# CPU.net
KiCad netlist of a schematic drawn in Altium Designer
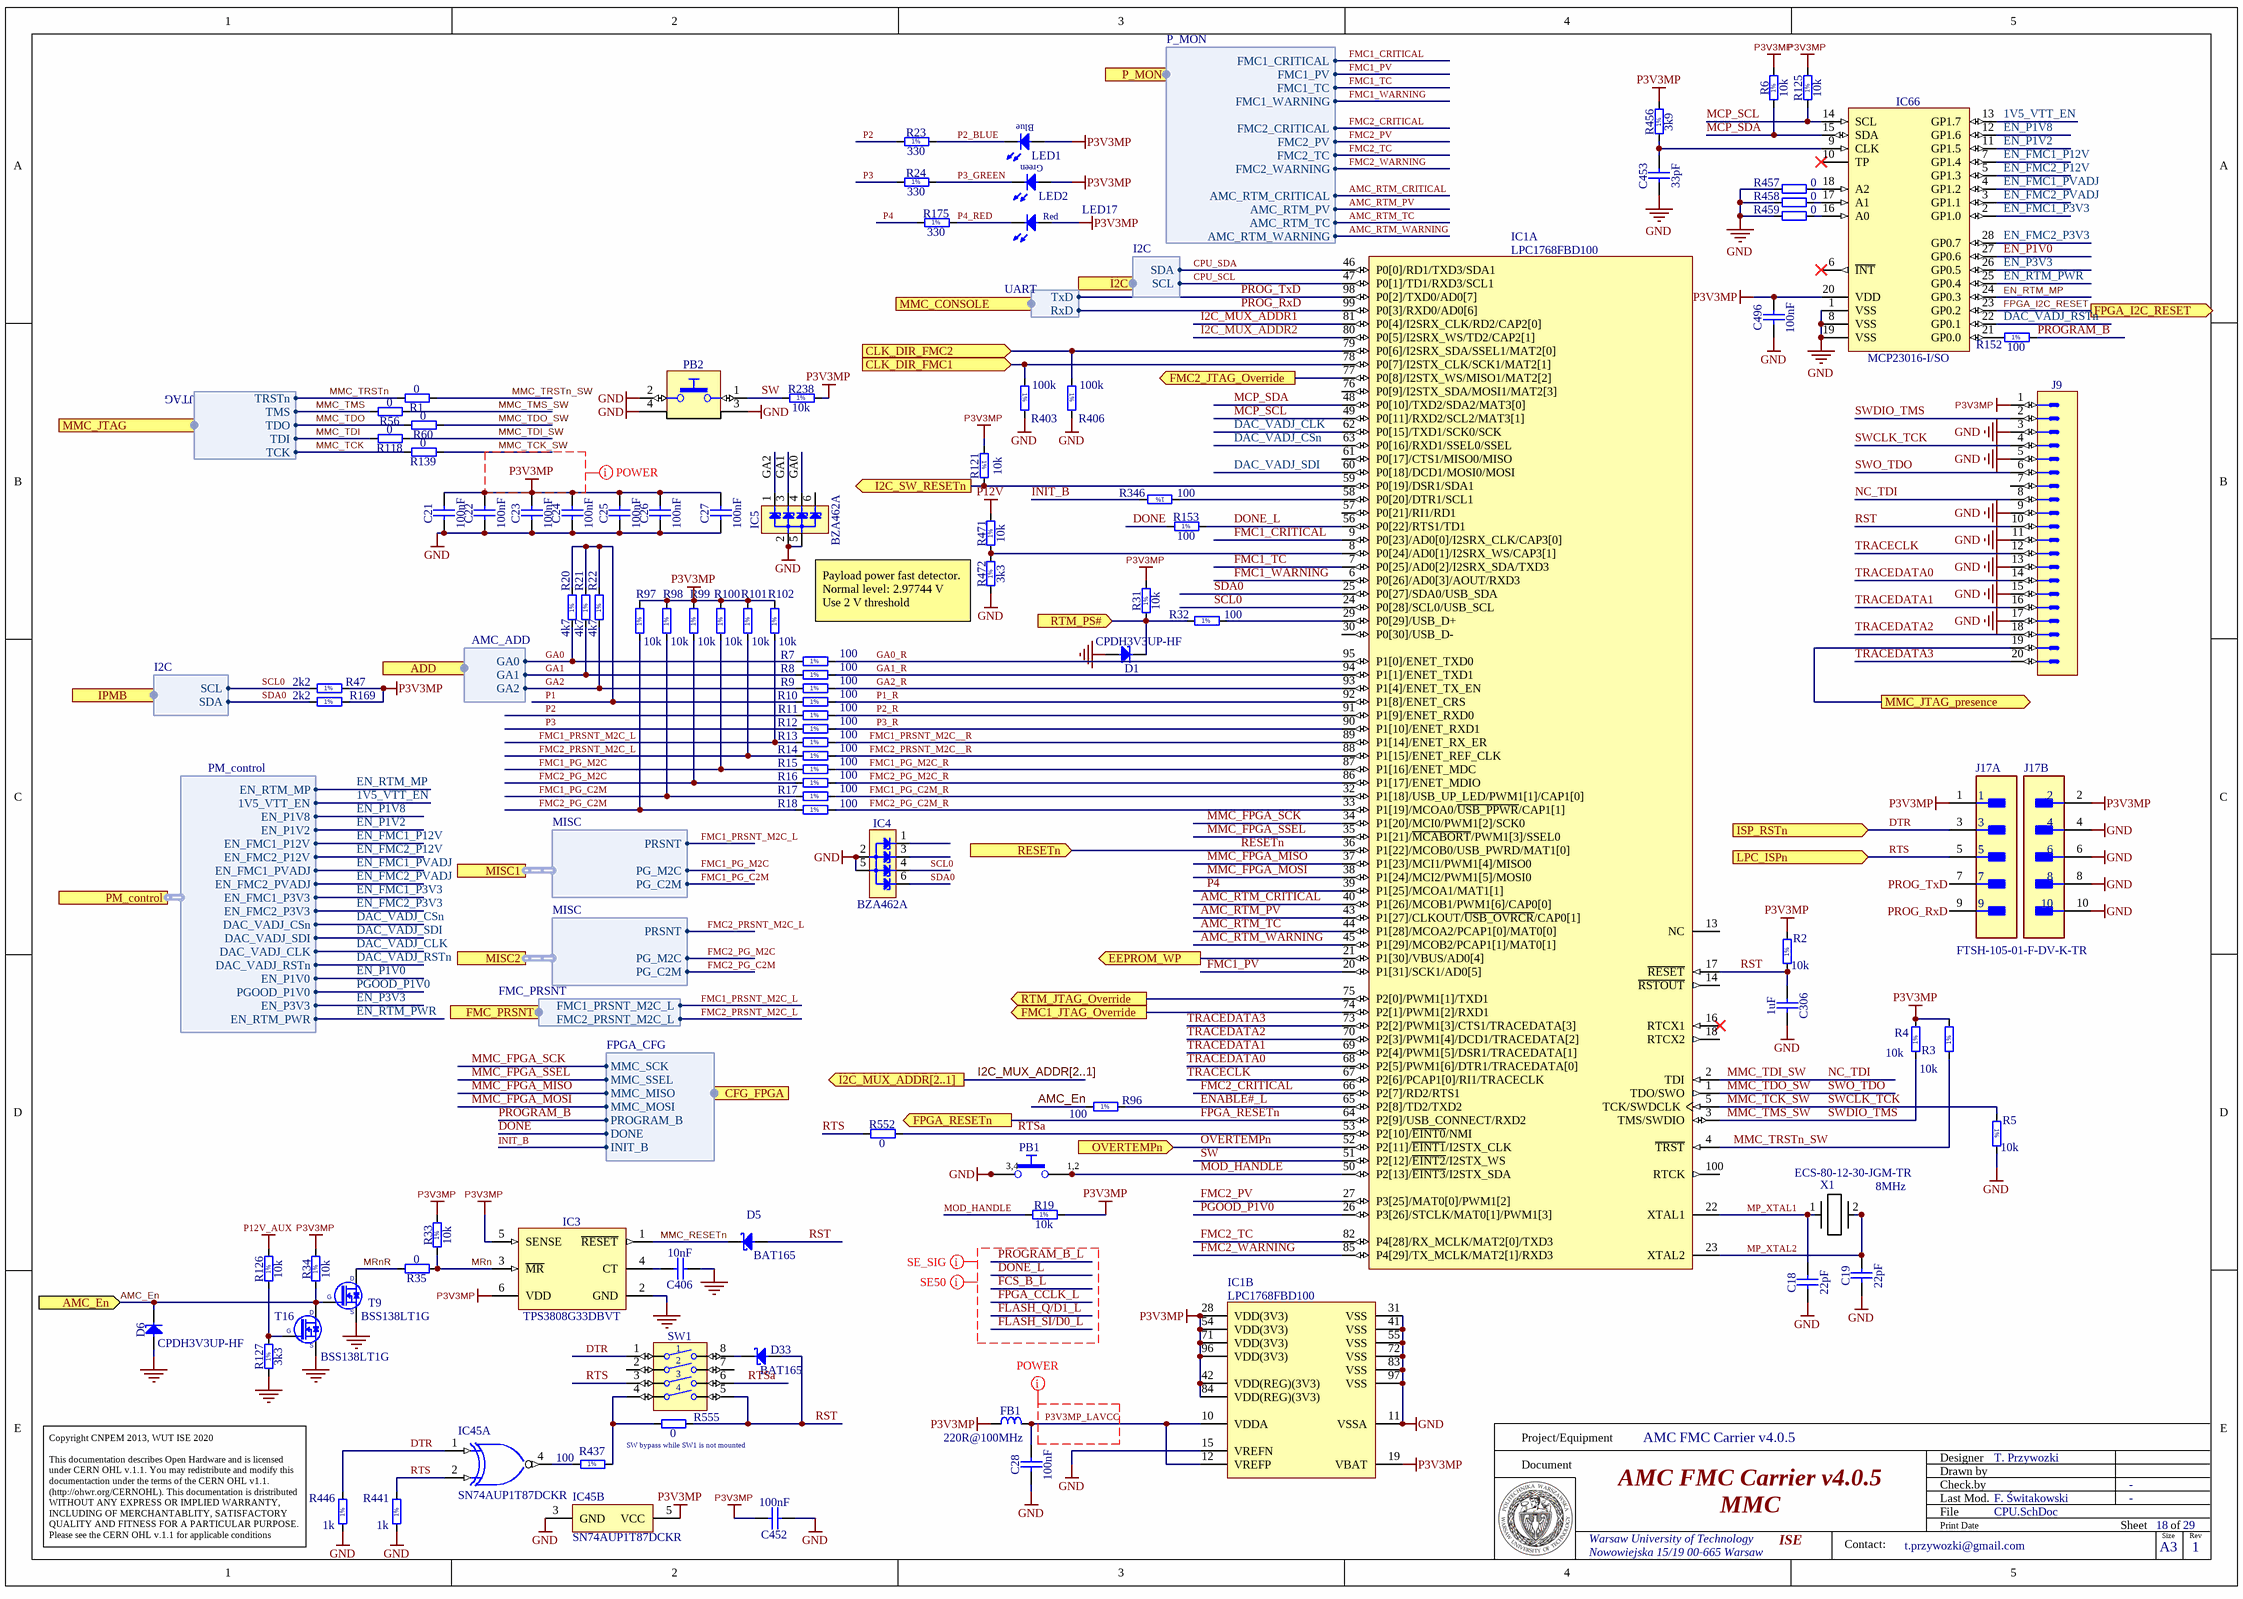
[diagram p0: CPU.SchDoc]

(export (version "E")
  (design (tool "Eeschema 10.0.6"))
  (components
    (comp (ref "C18")
      (value "22pF")
      (footprint "CAPC1005X55N")
      (description "Non-polarised capacitor")
      (fields
        (field (name "PART NUMBER") "CC0402_22PF_50V_5%_NP0")
        (field (name "VOLTAGE") "50V")
        (field (name "AUTHOR") "CERN DEM JLC")
      )
      (libsource (lib "Capacitors") (part "Capacitor - non polarized"))
    )
    (comp (ref "C19")
      (value "22pF")
      (footprint "CAPC1005X55N")
      (description "Non-polarised capacitor")
      (fields
        (field (name "PART NUMBER") "CC0402_22PF_50V_5%_NP0")
        (field (name "VOLTAGE") "50V")
        (field (name "AUTHOR") "CERN DEM JLC")
      )
      (libsource (lib "Capacitors") (part "Capacitor - non polarized"))
    )
    (comp (ref "C21")
      (value "100nF")
      (footprint "CAPC0603X33N")
      (description "Non-polarised capacitor")
      (fields
        (field (name "PART NUMBER") "CC0201_100NF_6.3V_10%_X5R")
        (field (name "VOLTAGE") "6.3V")
        (field (name "AUTHOR") "CERN DEM JLC")
      )
      (libsource (lib "Capacitors") (part "Capacitor - non polarized"))
    )
    (comp (ref "C22")
      (value "100nF")
      (footprint "CAPC0603X33N")
      (description "Non-polarised capacitor")
      (fields
        (field (name "PART NUMBER") "CC0201_100NF_6.3V_10%_X5R")
        (field (name "VOLTAGE") "6.3V")
        (field (name "AUTHOR") "CERN DEM JLC")
      )
      (libsource (lib "Capacitors") (part "Capacitor - non polarized"))
    )
    (comp (ref "C23")
      (value "100nF")
      (footprint "CAPC0603X33N")
      (description "Non-polarised capacitor")
      (fields
        (field (name "PART NUMBER") "CC0201_100NF_6.3V_10%_X5R")
        (field (name "VOLTAGE") "6.3V")
        (field (name "AUTHOR") "CERN DEM JLC")
      )
      (libsource (lib "Capacitors") (part "Capacitor - non polarized"))
    )
    (comp (ref "C24")
      (value "100nF")
      (footprint "CAPC0603X33N")
      (description "Non-polarised capacitor")
      (fields
        (field (name "PART NUMBER") "CC0201_100NF_6.3V_10%_X5R")
        (field (name "VOLTAGE") "6.3V")
        (field (name "AUTHOR") "CERN DEM JLC")
      )
      (libsource (lib "Capacitors") (part "Capacitor - non polarized"))
    )
    (comp (ref "C25")
      (value "100nF")
      (footprint "CAPC0603X33N")
      (description "Non-polarised capacitor")
      (fields
        (field (name "PART NUMBER") "CC0201_100NF_6.3V_10%_X5R")
        (field (name "VOLTAGE") "6.3V")
        (field (name "AUTHOR") "CERN DEM JLC")
      )
      (libsource (lib "Capacitors") (part "Capacitor - non polarized"))
    )
    (comp (ref "C26")
      (value "100nF")
      (footprint "CAPC0603X33N")
      (description "Non-polarised capacitor")
      (fields
        (field (name "PART NUMBER") "CC0201_100NF_6.3V_10%_X5R")
        (field (name "VOLTAGE") "6.3V")
        (field (name "AUTHOR") "CERN DEM JLC")
      )
      (libsource (lib "Capacitors") (part "Capacitor - non polarized"))
    )
    (comp (ref "C27")
      (value "100nF")
      (footprint "CAPC0603X33N")
      (description "Non-polarised capacitor")
      (fields
        (field (name "PART NUMBER") "CC0201_100NF_6.3V_10%_X5R")
        (field (name "VOLTAGE") "6.3V")
        (field (name "AUTHOR") "CERN DEM JLC")
      )
      (libsource (lib "Capacitors") (part "Capacitor - non polarized"))
    )
    (comp (ref "C28")
      (value "100nF")
      (footprint "CAPC0603X33N")
      (description "Non-polarised capacitor")
      (fields
        (field (name "PART NUMBER") "CC0201_100NF_6.3V_10%_X5R")
        (field (name "VOLTAGE") "6.3V")
        (field (name "AUTHOR") "CERN DEM JLC")
      )
      (libsource (lib "Capacitors") (part "Capacitor - non polarized"))
    )
    (comp (ref "C306")
      (value "1uF")
      (footprint "CAPC1608X87N")
      (description "Non-polarised capacitor")
      (fields
        (field (name "PART NUMBER") "CC0603_1UF_16V_10%_X7R")
        (field (name "VOLTAGE") "16V")
        (field (name "AUTHOR") "CERN DEM JLC")
      )
      (libsource (lib "Capacitors") (part "Capacitor - non polarized"))
    )
    (comp (ref "C406")
      (value "10nF")
      (footprint "CAPC1005X55N")
      (description "Non-polarised capacitor")
      (fields
        (field (name "MANUFACTURER PART NUMBER") "CC0402_10NF_16V_10%_X7R")
        (field (name "MANUFACTURER") "GENERIC")
        (field (name "AUTHOR") "CERN DEM JLC")
      )
      (libsource (lib "Capacitors") (part "Capacitor - non polarized"))
    )
    (comp (ref "C452")
      (value "100nF")
      (footprint "CAPC0603X33N")
      (description "Non-polarised capacitor")
      (fields
        (field (name "PART NUMBER") "CC0201_100NF_6.3V_10%_X5R")
        (field (name "VOLTAGE") "6.3V")
        (field (name "AUTHOR") "CERN DEM JLC")
      )
      (libsource (lib "Capacitors") (part "Capacitor - non polarized"))
    )
    (comp (ref "C453")
      (value "33pF")
      (footprint "CAPC1005X55N")
      (description "Non-polarised capacitor")
      (fields
        (field (name "PART NUMBER") "CC0402_33PF_50V_5%_C0G")
        (field (name "VOLTAGE") "50V")
        (field (name "AUTHOR") "CERN DEM JLC")
      )
      (libsource (lib "Capacitors") (part "Capacitor - non polarized"))
    )
    (comp (ref "C496")
      (value "100nF")
      (footprint "CAPC0603X33N")
      (description "Non-polarised capacitor")
      (fields
        (field (name "PART NUMBER") "CC0201_100NF_6.3V_10%_X5R")
        (field (name "VOLTAGE") "6.3V")
        (field (name "AUTHOR") "CERN DEM JLC")
      )
      (libsource (lib "Capacitors") (part "Capacitor - non polarized"))
    )
    (comp (ref "D1")
      (value "CPDH3V3UP-HF")
      (footprint "SODFL1608X65N")
      (description "ESD protection diode")
      (fields (field (name "MANUFACTURER") "Comchip Technology") (field (name "AUTHOR") "CERN DEM JLC"))
      (libsource (lib "ICs And Semiconductors") (part "Diode ESD"))
    )
    (comp (ref "D5")
      (value "BAT165")
      (footprint "SOD2512X110N")
      (description "Schottky Diode")
      (fields
        (field (name "MANUFACTURER") "INFINEON")
        (field (name "VOLTAGE") "40V")
        (field (name "AUTHOR") "CERN DEM JLC")
      )
      (libsource (lib "ICs And Semiconductors") (part "Diode Schottky"))
    )
    (comp (ref "D6")
      (value "CPDH3V3UP-HF")
      (footprint "SODFL1608X65N")
      (description "ESD protection diode")
      (fields (field (name "MANUFACTURER") "Comchip Technology") (field (name "AUTHOR") "CERN DEM JLC"))
      (libsource (lib "ICs And Semiconductors") (part "Diode ESD"))
    )
    (comp (ref "D33")
      (value "BAT165")
      (footprint "SOD2512X110N")
      (description "Schottky Diode")
      (fields
        (field (name "MANUFACTURER") "INFINEON")
        (field (name "VOLTAGE") "40V")
        (field (name "AUTHOR") "CERN DEM JLC")
      )
      (libsource (lib "ICs And Semiconductors") (part "Diode Schottky"))
    )
    (comp (ref "FB1")
      (value "220R@100MHz")
      (footprint "INDC2012X105N")
      (description "Inductor")
      (fields
        (field (name "PART NUMBER") "IND0805_MURATA_BLM21PG221SN1D")
        (field (name "POWER") "2A")
        (field (name "AUTHOR") "CERN DEM JLC")
      )
      (libsource (lib "Inductors & Transformers") (part "Inductor"))
    )
    (comp (ref "IC1")
      (value "LPC1768FBD100")
      (footprint "QFP50P1600X1600X160-100N")
      (description "LPC1768 Series 64kB 100MHz 32-Bit ARM Cortex-M3 Microcontroller")
      (fields (field (name "MANUFACTURER") "NXP SEMICONDUCTORS") (field (name "AUTHOR") "CERN DEM JLC"))
      (libsource (lib "ICs And Semiconductors") (part "LPC1768FBD100"))
    )
    (comp (ref "IC3")
      (value "TPS3808G33DBVT")
      (footprint "SOT95P280X145-6N")
      (description "Low Quiescent Current, Programmable-Delay Supervisory Circuit")
      (fields (field (name "MANUFACTURER") "TEXAS INSTRUMENTS") (field (name "AUTHOR") "CERN DEM JLC"))
      (libsource (lib "ICs And Semiconductors") (part "TPS3808xxxDBV"))
    )
    (comp (ref "IC4")
      (value "BZA462A")
      (footprint "SOT95P275X110-6N")
      (description "Quadruple ESD Transient Voltage Suppressor")
      (fields
        (field (name "VOLTAGE") "15kV")
        (field (name "POWER") "24W")
        (field (name "AUTHOR") "CERN DEM JLC")
      )
      (libsource (lib "ICs And Semiconductors") (part "BZA462A"))
    )
    (comp (ref "IC5")
      (value "BZA462A")
      (footprint "SOT95P275X110-6N")
      (description "Quadruple ESD Transient Voltage Suppressor")
      (fields
        (field (name "VOLTAGE") "15kV")
        (field (name "POWER") "24W")
        (field (name "AUTHOR") "CERN DEM JLC")
      )
      (libsource (lib "") (part "BZA462A_1"))
    )
    (comp (ref "IC45")
      (value "SN74AUP1T87DCKR")
      (footprint "DCK0005A_L")
      (fields
        (field (name "GENERIC PART NUMBER") "SN74AUP1T87")
        (field (name "MANUFACTURER") "Texas Instruments")
      )
      (libsource (lib "") (part "TI-SN74AUP1T87-DCK0005A-5_1"))
    )
    (comp (ref "IC66")
      (value "MCP23016-I/SO")
      (footprint "SOIC127P1030X265-28N")
      (description "16-bit I/O I2C I/O Expander")
      (fields (field (name "MANUFACTURER") "MICROCHIP TECHNOLOGY") (field (name "AUTHOR") "CERN DEM JLC"))
      (libsource (lib "ICs And Semiconductors") (part "MCP23016-I/SO"))
    )
    (comp (ref "J9")
      (value "Header 20")
      (footprint "SAMTEC_FTSH-110-01-F-DV-K")
      (description "Connector 20 Male")
      (fields
        (field (name "PART NUMBER") "SAMTEC_FTSH-110-01-F-DV-K")
        (field (name "MANUFACTURER") "SAMTEC")
        (field (name "AUTHOR") "CERN DEM JLC")
      )
      (libsource (lib "Connectors") (part "Connector 20 Male"))
    )
    (comp (ref "J17")
      (value "FTSH-105-01-F-DV-K-TR")
      (footprint "FP-FTSH-105-01-F-DV-K-TR-MFG")
      (description "CONN HEADER SMD 10POS 1.27MM")
      (libsource (lib "") (part "544f42128f4185dcb88ce1ce9bf1982_1"))
    )
    (comp (ref "LED1")
      (value "Blue")
      (footprint "LED_AVAGO_HSME-C120rev")
      (description "LED Blue Avago C120")
      (fields
        (field (name "PART NUMBER") "LED_AVAGO_HSMR-C120")
        (field (name "MANUFACTURER") "AVAGO TECHNOLOGIES")
        (field (name "AUTHOR") "CERN DEM JMW")
      )
      (libsource (lib "LIBRARY_SCH") (part "LED_SMD_90deg_mini_B"))
    )
    (comp (ref "LED2")
      (value "Green")
      (footprint "LED_AVAGO_HSME-C120rev")
      (description "LED Green Avago C120")
      (fields
        (field (name "PART NUMBER") "LED_AVAGO_HSME-C120")
        (field (name "MANUFACTURER") "AVAGO TECHNOLOGIES")
        (field (name "AUTHOR") "CERN DEM JMW")
      )
      (libsource (lib "LIBRARY_SCH") (part "LED_SMD_90deg_mini_G"))
    )
    (comp (ref "LED17")
      (value "Red")
      (footprint "LED_KINGBRIGHT_KPH-1608SURCK")
      (description "LED Red 1C 2A")
      (fields
        (field (name "PART NUMBER") "LED_KINGBRIGHT_KPH-1608SURCK")
        (field (name "MANUFACTURER") "KINGBRIGHT")
        (field (name "AUTHOR") "CERN DEM JLC")
      )
      (libsource (lib "ICs And Semiconductors") (part "LED Red 1C 2A"))
    )
    (comp (ref "PB1")
      (value "Push Button")
      (footprint "SW_C&K_HDT0001")
      (description "Push-Button Switch SPDT")
      (fields
        (field (name "PART NUMBER") "SW_C&K_HDT0001")
        (field (name "MANUFACTURER") "C&K")
        (field (name "AUTHOR") "CERN DEM JLC")
      )
      (libsource (lib "Eletro-mechanical") (part "PB SPST 12NO-34NO"))
    )
    (comp (ref "PB2")
      (value "Push Button")
      (footprint "PB_ALPS_SKHHLMA010")
      (description "Push-Button Switch SPDT")
      (fields
        (field (name "PART NUMBER") "PB_ALPS_SKHHLMA010")
        (field (name "MANUFACTURER") "ALPS")
        (field (name "AUTHOR") "CERN DEM JLC")
      )
      (libsource (lib "Eletro-mechanical") (part "PB SPST 1NO-2NO 34CASE"))
    )
    (comp (ref "R1")
      (value "0")
      (footprint "RESC1005X40N")
      (description "Resistor")
      (fields
        (field (name "MANUFACTURER PART NUMBER") "R0402_0R_JUMPER")
        (field (name "MANUFACTURER") "GENERIC")
        (field (name "AUTHOR") "CERN DEM JLC")
      )
      (libsource (lib "Resistors") (part "Resistor"))
    )
    (comp (ref "R2")
      (value "10k")
      (footprint "RESC1005X40N")
      (description "Resistor - 1%")
      (fields
        (field (name "PART NUMBER") "R0402_10K_1%_0.0625W_100PPM")
        (field (name "POWER") "0.0625W")
        (field (name "AUTHOR") "CERN DEM JLC")
      )
      (libsource (lib "Resistors") (part "Resistor - 1%"))
    )
    (comp (ref "R3")
      (value "10k")
      (footprint "RESC1005X40N")
      (description "Resistor - 1%")
      (fields
        (field (name "PART NUMBER") "R0402_10K_1%_0.0625W_100PPM")
        (field (name "POWER") "0.0625W")
        (field (name "AUTHOR") "CERN DEM JLC")
      )
      (libsource (lib "Resistors") (part "Resistor - 1%"))
    )
    (comp (ref "R4")
      (value "10k")
      (footprint "RESC1005X40N")
      (description "Resistor - 1%")
      (fields
        (field (name "PART NUMBER") "R0402_10K_1%_0.0625W_100PPM")
        (field (name "POWER") "0.0625W")
        (field (name "AUTHOR") "CERN DEM JLC")
      )
      (libsource (lib "Resistors") (part "Resistor - 1%"))
    )
    (comp (ref "R5")
      (value "10k")
      (footprint "RESC1005X40N")
      (description "Resistor - 1%")
      (fields
        (field (name "PART NUMBER") "R0402_10K_1%_0.0625W_100PPM")
        (field (name "POWER") "0.0625W")
        (field (name "AUTHOR") "CERN DEM JLC")
      )
      (libsource (lib "Resistors") (part "Resistor - 1%"))
    )
    (comp (ref "R6")
      (value "10k")
      (footprint "RESC1005X40N")
      (description "Resistor - 1%")
      (fields
        (field (name "MANUFACTURER PART NUMBER") "R0402_10K_1%_0.0625W_100PPM")
        (field (name "MANUFACTURER") "GENERIC")
        (field (name "AUTHOR") "CERN DEM JLC")
      )
      (libsource (lib "Resistors") (part "Resistor - 1%"))
    )
    (comp (ref "R7")
      (value "100")
      (footprint "RESC1005X40N")
      (description "Resistor - 1%")
      (fields
        (field (name "PART NUMBER") "R0402_100R_1%_0.0625W_100PPM")
        (field (name "POWER") "0.0625W")
        (field (name "AUTHOR") "CERN DEM JLC")
      )
      (libsource (lib "Resistors") (part "Resistor - 1%"))
    )
    (comp (ref "R8")
      (value "100")
      (footprint "RESC1005X40N")
      (description "Resistor - 1%")
      (fields
        (field (name "PART NUMBER") "R0402_100R_1%_0.0625W_100PPM")
        (field (name "POWER") "0.0625W")
        (field (name "AUTHOR") "CERN DEM JLC")
      )
      (libsource (lib "Resistors") (part "Resistor - 1%"))
    )
    (comp (ref "R9")
      (value "100")
      (footprint "RESC1005X40N")
      (description "Resistor - 1%")
      (fields
        (field (name "PART NUMBER") "R0402_100R_1%_0.0625W_100PPM")
        (field (name "POWER") "0.0625W")
        (field (name "AUTHOR") "CERN DEM JLC")
      )
      (libsource (lib "Resistors") (part "Resistor - 1%"))
    )
    (comp (ref "R10")
      (value "100")
      (footprint "RESC1005X40N")
      (description "Resistor - 1%")
      (fields
        (field (name "PART NUMBER") "R0402_100R_1%_0.0625W_100PPM")
        (field (name "POWER") "0.0625W")
        (field (name "AUTHOR") "CERN DEM JLC")
      )
      (libsource (lib "Resistors") (part "Resistor - 1%"))
    )
    (comp (ref "R11")
      (value "100")
      (footprint "RESC1005X40N")
      (description "Resistor - 1%")
      (fields
        (field (name "PART NUMBER") "R0402_100R_1%_0.0625W_100PPM")
        (field (name "POWER") "0.0625W")
        (field (name "AUTHOR") "CERN DEM JLC")
      )
      (libsource (lib "Resistors") (part "Resistor - 1%"))
    )
    (comp (ref "R12")
      (value "100")
      (footprint "RESC1005X40N")
      (description "Resistor - 1%")
      (fields
        (field (name "PART NUMBER") "R0402_100R_1%_0.0625W_100PPM")
        (field (name "POWER") "0.0625W")
        (field (name "AUTHOR") "CERN DEM JLC")
      )
      (libsource (lib "Resistors") (part "Resistor - 1%"))
    )
    (comp (ref "R13")
      (value "100")
      (footprint "RESC1005X40N")
      (description "Resistor - 1%")
      (fields
        (field (name "PART NUMBER") "R0402_100R_1%_0.0625W_100PPM")
        (field (name "POWER") "0.0625W")
        (field (name "AUTHOR") "CERN DEM JLC")
      )
      (libsource (lib "Resistors") (part "Resistor - 1%"))
    )
    (comp (ref "R14")
      (value "100")
      (footprint "RESC1005X40N")
      (description "Resistor - 1%")
      (fields
        (field (name "PART NUMBER") "R0402_100R_1%_0.0625W_100PPM")
        (field (name "POWER") "0.0625W")
        (field (name "AUTHOR") "CERN DEM JLC")
      )
      (libsource (lib "Resistors") (part "Resistor - 1%"))
    )
    (comp (ref "R15")
      (value "100")
      (footprint "RESC1005X40N")
      (description "Resistor - 1%")
      (fields
        (field (name "PART NUMBER") "R0402_100R_1%_0.0625W_100PPM")
        (field (name "POWER") "0.0625W")
        (field (name "AUTHOR") "CERN DEM JLC")
      )
      (libsource (lib "Resistors") (part "Resistor - 1%"))
    )
    (comp (ref "R16")
      (value "100")
      (footprint "RESC1005X40N")
      (description "Resistor - 1%")
      (fields
        (field (name "PART NUMBER") "R0402_100R_1%_0.0625W_100PPM")
        (field (name "POWER") "0.0625W")
        (field (name "AUTHOR") "CERN DEM JLC")
      )
      (libsource (lib "Resistors") (part "Resistor - 1%"))
    )
    (comp (ref "R17")
      (value "100")
      (footprint "RESC1005X40N")
      (description "Resistor - 1%")
      (fields
        (field (name "PART NUMBER") "R0402_100R_1%_0.0625W_100PPM")
        (field (name "POWER") "0.0625W")
        (field (name "AUTHOR") "CERN DEM JLC")
      )
      (libsource (lib "Resistors") (part "Resistor - 1%"))
    )
    (comp (ref "R18")
      (value "100")
      (footprint "RESC1005X40N")
      (description "Resistor - 1%")
      (fields
        (field (name "PART NUMBER") "R0402_100R_1%_0.0625W_100PPM")
        (field (name "POWER") "0.0625W")
        (field (name "AUTHOR") "CERN DEM JLC")
      )
      (libsource (lib "Resistors") (part "Resistor - 1%"))
    )
    (comp (ref "R19")
      (value "10k")
      (footprint "RESC1005X40N")
      (description "Resistor - 1%")
      (fields
        (field (name "PART NUMBER") "R0402_10K_1%_0.0625W_100PPM")
        (field (name "POWER") "0.0625W")
        (field (name "AUTHOR") "CERN DEM JLC")
      )
      (libsource (lib "Resistors") (part "Resistor - 1%"))
    )
    (comp (ref "R20")
      (value "4k7")
      (footprint "RESC1005X40N")
      (description "Resistor - 1%")
      (fields
        (field (name "PART NUMBER") "R0402_4K7_1%_0.0625W_100PPM")
        (field (name "POWER") "0.0625W")
        (field (name "AUTHOR") "CERN DEM JLC")
      )
      (libsource (lib "Resistors") (part "Resistor - 1%"))
    )
    (comp (ref "R21")
      (value "4k7")
      (footprint "RESC1005X40N")
      (description "Resistor - 1%")
      (fields
        (field (name "PART NUMBER") "R0402_4K7_1%_0.0625W_100PPM")
        (field (name "POWER") "0.0625W")
        (field (name "AUTHOR") "CERN DEM JLC")
      )
      (libsource (lib "Resistors") (part "Resistor - 1%"))
    )
    (comp (ref "R22")
      (value "4k7")
      (footprint "RESC1005X40N")
      (description "Resistor - 1%")
      (fields
        (field (name "PART NUMBER") "R0402_4K7_1%_0.0625W_100PPM")
        (field (name "POWER") "0.0625W")
        (field (name "AUTHOR") "CERN DEM JLC")
      )
      (libsource (lib "Resistors") (part "Resistor - 1%"))
    )
    (comp (ref "R23")
      (value "330")
      (footprint "RESC1005X40N")
      (description "Resistor - 1%")
      (fields
        (field (name "PART NUMBER") "R0402_330R_1%_0.0625W_100PPM")
        (field (name "POWER") "0.0625W")
        (field (name "AUTHOR") "CERN DEM JLC")
      )
      (libsource (lib "Resistors") (part "Resistor - 1%"))
    )
    (comp (ref "R24")
      (value "330")
      (footprint "RESC1005X40N")
      (description "Resistor - 1%")
      (fields
        (field (name "PART NUMBER") "R0402_330R_1%_0.0625W_100PPM")
        (field (name "POWER") "0.0625W")
        (field (name "AUTHOR") "CERN DEM JLC")
      )
      (libsource (lib "Resistors") (part "Resistor - 1%"))
    )
    (comp (ref "R31")
      (value "10k")
      (footprint "RESC1005X40N")
      (description "Resistor - 1%")
      (fields
        (field (name "MANUFACTURER PART NUMBER") "R0402_10K_1%_0.0625W_100PPM")
        (field (name "MANUFACTURER") "GENERIC")
        (field (name "AUTHOR") "CERN DEM JLC")
      )
      (libsource (lib "Resistors") (part "Resistor - 1%"))
    )
    (comp (ref "R32")
      (value "100")
      (footprint "RESC1005X40N")
      (description "Resistor - 1%")
      (fields
        (field (name "MANUFACTURER PART NUMBER") "R0402_100R_1%_0.1W_100PPM_50V")
        (field (name "MANUFACTURER") "GENERIC")
        (field (name "AUTHOR") "CERN DEM JLC")
      )
      (libsource (lib "Resistors") (part "Resistor - 1%"))
    )
    (comp (ref "R33")
      (value "10k")
      (footprint "RESC1005X40N")
      (description "Resistor - 1%")
      (fields
        (field (name "MANUFACTURER PART NUMBER") "R0402_10K_1%_0.0625W_100PPM")
        (field (name "MANUFACTURER") "GENERIC")
        (field (name "AUTHOR") "CERN DEM JLC")
      )
      (libsource (lib "Resistors") (part "Resistor - 1%"))
    )
    (comp (ref "R34")
      (value "10k")
      (footprint "RESC1005X40N")
      (description "Resistor - 1%")
      (fields
        (field (name "MANUFACTURER PART NUMBER") "R0402_10K_1%_0.0625W_100PPM")
        (field (name "MANUFACTURER") "GENERIC")
        (field (name "AUTHOR") "CERN DEM JLC")
      )
      (libsource (lib "Resistors") (part "Resistor - 1%"))
    )
    (comp (ref "R35")
      (value "0")
      (footprint "RESC1005X40N")
      (description "Resistor")
      (fields
        (field (name "MANUFACTURER PART NUMBER") "R0402_0R_JUMPER")
        (field (name "MANUFACTURER") "GENERIC")
        (field (name "AUTHOR") "CERN DEM JLC")
      )
      (libsource (lib "Resistors") (part "Resistor"))
    )
    (comp (ref "R47")
      (value "2k2")
      (footprint "RESC1005X40N")
      (description "Resistor - 1%")
      (fields
        (field (name "PART NUMBER") "R0402_2K2_1%_0.0625W_100PPM")
        (field (name "POWER") "0.0625W")
        (field (name "AUTHOR") "CERN DEM JLC")
      )
      (libsource (lib "Resistors") (part "Resistor - 1%"))
    )
    (comp (ref "R56")
      (value "0")
      (footprint "RESC1005X40N")
      (description "Resistor")
      (fields
        (field (name "MANUFACTURER PART NUMBER") "R0402_0R_JUMPER")
        (field (name "MANUFACTURER") "GENERIC")
        (field (name "AUTHOR") "CERN DEM JLC")
      )
      (libsource (lib "Resistors") (part "Resistor"))
    )
    (comp (ref "R60")
      (value "0")
      (footprint "RESC1005X40N")
      (description "Resistor")
      (fields
        (field (name "MANUFACTURER PART NUMBER") "R0402_0R_JUMPER")
        (field (name "MANUFACTURER") "GENERIC")
        (field (name "AUTHOR") "CERN DEM JLC")
      )
      (libsource (lib "Resistors") (part "Resistor"))
    )
    (comp (ref "R96")
      (value "100")
      (footprint "RESC1005X40N")
      (description "Resistor - 1%")
      (fields
        (field (name "PART NUMBER") "R0402_100R_1%_0.0625W_100PPM")
        (field (name "POWER") "0.0625W")
        (field (name "AUTHOR") "CERN DEM JLC")
      )
      (libsource (lib "Resistors") (part "Resistor - 1%"))
    )
    (comp (ref "R97")
      (value "10k")
      (footprint "RESC1005X40N")
      (description "Resistor - 1%")
      (fields
        (field (name "PART NUMBER") "R0402_10K_1%_0.0625W_100PPM")
        (field (name "POWER") "0.0625W")
        (field (name "AUTHOR") "CERN DEM JLC")
      )
      (libsource (lib "Resistors") (part "Resistor - 1%"))
    )
    (comp (ref "R98")
      (value "10k")
      (footprint "RESC1005X40N")
      (description "Resistor - 1%")
      (fields
        (field (name "PART NUMBER") "R0402_10K_1%_0.0625W_100PPM")
        (field (name "POWER") "0.0625W")
        (field (name "AUTHOR") "CERN DEM JLC")
      )
      (libsource (lib "Resistors") (part "Resistor - 1%"))
    )
    (comp (ref "R99")
      (value "10k")
      (footprint "RESC1005X40N")
      (description "Resistor - 1%")
      (fields
        (field (name "PART NUMBER") "R0402_10K_1%_0.0625W_100PPM")
        (field (name "POWER") "0.0625W")
        (field (name "AUTHOR") "CERN DEM JLC")
      )
      (libsource (lib "Resistors") (part "Resistor - 1%"))
    )
    (comp (ref "R100")
      (value "10k")
      (footprint "RESC1005X40N")
      (description "Resistor - 1%")
      (fields
        (field (name "PART NUMBER") "R0402_10K_1%_0.0625W_100PPM")
        (field (name "POWER") "0.0625W")
        (field (name "AUTHOR") "CERN DEM JLC")
      )
      (libsource (lib "Resistors") (part "Resistor - 1%"))
    )
    (comp (ref "R101")
      (value "10k")
      (footprint "RESC1005X40N")
      (description "Resistor - 1%")
      (fields
        (field (name "PART NUMBER") "R0402_10K_1%_0.0625W_100PPM")
        (field (name "POWER") "0.0625W")
        (field (name "AUTHOR") "CERN DEM JLC")
      )
      (libsource (lib "Resistors") (part "Resistor - 1%"))
    )
    (comp (ref "R102")
      (value "10k")
      (footprint "RESC1005X40N")
      (description "Resistor - 1%")
      (fields
        (field (name "PART NUMBER") "R0402_10K_1%_0.0625W_100PPM")
        (field (name "POWER") "0.0625W")
        (field (name "AUTHOR") "CERN DEM JLC")
      )
      (libsource (lib "Resistors") (part "Resistor - 1%"))
    )
    (comp (ref "R118")
      (value "0")
      (footprint "RESC1005X40N")
      (description "Resistor")
      (fields
        (field (name "MANUFACTURER PART NUMBER") "R0402_0R_JUMPER")
        (field (name "MANUFACTURER") "GENERIC")
        (field (name "AUTHOR") "CERN DEM JLC")
      )
      (libsource (lib "Resistors") (part "Resistor"))
    )
    (comp (ref "R121")
      (value "10k")
      (footprint "RESC1005X40N")
      (description "Resistor - 1%")
      (fields
        (field (name "MANUFACTURER PART NUMBER") "R0402_10K_1%_0.0625W_100PPM")
        (field (name "MANUFACTURER") "GENERIC")
        (field (name "AUTHOR") "CERN DEM JLC")
      )
      (libsource (lib "Resistors") (part "Resistor - 1%"))
    )
    (comp (ref "R125")
      (value "10k")
      (footprint "RESC1005X40N")
      (description "Resistor - 1%")
      (fields
        (field (name "MANUFACTURER PART NUMBER") "R0402_10K_1%_0.0625W_100PPM")
        (field (name "MANUFACTURER") "GENERIC")
        (field (name "AUTHOR") "CERN DEM JLC")
      )
      (libsource (lib "Resistors") (part "Resistor - 1%"))
    )
    (comp (ref "R126")
      (value "10k")
      (footprint "RESC1005X40N")
      (description "Resistor - 1%")
      (fields
        (field (name "MANUFACTURER PART NUMBER") "R0402_10K_1%_0.0625W_100PPM")
        (field (name "MANUFACTURER") "GENERIC")
        (field (name "AUTHOR") "CERN DEM JLC")
      )
      (libsource (lib "Resistors") (part "Resistor - 1%"))
    )
    (comp (ref "R127")
      (value "3k3")
      (footprint "RESC1608X55N")
      (description "Resistor - 1%")
      (fields
        (field (name "PART NUMBER") "R0603_3K3_1%_0.1W_100PPM")
        (field (name "POWER") "0.1W")
        (field (name "AUTHOR") "CERN DEM JLC")
      )
      (libsource (lib "Resistors") (part "Resistor - 1%"))
    )
    (comp (ref "R139")
      (value "0")
      (footprint "RESC1005X40N")
      (description "Resistor")
      (fields
        (field (name "MANUFACTURER PART NUMBER") "R0402_0R_JUMPER")
        (field (name "MANUFACTURER") "GENERIC")
        (field (name "AUTHOR") "CERN DEM JLC")
      )
      (libsource (lib "Resistors") (part "Resistor"))
    )
    (comp (ref "R152")
      (value "100")
      (footprint "RESC1005X40N")
      (description "Resistor - 1%")
      (fields
        (field (name "PART NUMBER") "R0402_100R_1%_0.0625W_100PPM")
        (field (name "POWER") "0.0625W")
        (field (name "AUTHOR") "CERN DEM JLC")
      )
      (libsource (lib "Resistors") (part "Resistor - 1%"))
    )
    (comp (ref "R153")
      (value "100")
      (footprint "RESC1005X40N")
      (description "Resistor - 1%")
      (fields
        (field (name "PART NUMBER") "R0402_100R_1%_0.0625W_100PPM")
        (field (name "POWER") "0.0625W")
        (field (name "AUTHOR") "CERN DEM JLC")
      )
      (libsource (lib "Resistors") (part "Resistor - 1%"))
    )
    (comp (ref "R169")
      (value "2k2")
      (footprint "RESC1005X40N")
      (description "Resistor - 1%")
      (fields
        (field (name "PART NUMBER") "R0402_2K2_1%_0.0625W_100PPM")
        (field (name "POWER") "0.0625W")
        (field (name "AUTHOR") "CERN DEM JLC")
      )
      (libsource (lib "Resistors") (part "Resistor - 1%"))
    )
    (comp (ref "R175")
      (value "330")
      (footprint "RESC1005X40N")
      (description "Resistor - 1%")
      (fields
        (field (name "PART NUMBER") "R0402_330R_1%_0.0625W_100PPM")
        (field (name "POWER") "0.0625W")
        (field (name "AUTHOR") "CERN DEM JLC")
      )
      (libsource (lib "Resistors") (part "Resistor - 1%"))
    )
    (comp (ref "R238")
      (value "10k")
      (footprint "RESC1005X40N")
      (description "Resistor - 1%")
      (fields
        (field (name "PART NUMBER") "R0402_10K_1%_0.0625W_100PPM")
        (field (name "POWER") "0.0625W")
        (field (name "AUTHOR") "CERN DEM JLC")
      )
      (libsource (lib "Resistors") (part "Resistor - 1%"))
    )
    (comp (ref "R346")
      (value "100")
      (footprint "RESC1005X40N")
      (description "Resistor - 1%")
      (fields
        (field (name "PART NUMBER") "R0402_100R_1%_0.0625W_100PPM")
        (field (name "POWER") "0.0625W")
        (field (name "AUTHOR") "CERN DEM JLC")
      )
      (libsource (lib "Resistors") (part "Resistor - 1%"))
    )
    (comp (ref "R403")
      (value "100k")
      (footprint "RESC1005X40N")
      (description "Resistor - 1%")
      (fields
        (field (name "PART NUMBER") "R0402_100K_1%_0.0625W_100PPM")
        (field (name "POWER") "0.0625W")
        (field (name "AUTHOR") "CERN DEM JLC")
      )
      (libsource (lib "Resistors") (part "Resistor - 1%"))
    )
    (comp (ref "R406")
      (value "100k")
      (footprint "RESC1005X40N")
      (description "Resistor - 1%")
      (fields
        (field (name "PART NUMBER") "R0402_100K_1%_0.0625W_100PPM")
        (field (name "POWER") "0.0625W")
        (field (name "AUTHOR") "CERN DEM JLC")
      )
      (libsource (lib "Resistors") (part "Resistor - 1%"))
    )
    (comp (ref "R437")
      (value "100")
      (footprint "RESC1005X40N")
      (description "Resistor - 1%")
      (fields
        (field (name "MANUFACTURER PART NUMBER") "R0402_100R_1%_0.1W_100PPM_50V")
        (field (name "MANUFACTURER") "GENERIC")
        (field (name "AUTHOR") "CERN DEM JLC")
      )
      (libsource (lib "Resistors") (part "Resistor - 1%"))
    )
    (comp (ref "R441")
      (value "1k")
      (footprint "RESC1005X40N")
      (description "Resistor - 1%")
      (fields
        (field (name "PART NUMBER") "R0402_1K_1%_0.0625W_100PPM")
        (field (name "POWER") "0.0625W")
        (field (name "AUTHOR") "CERN DEM JLC")
      )
      (libsource (lib "Resistors") (part "Resistor - 1%"))
    )
    (comp (ref "R446")
      (value "1k")
      (footprint "RESC1005X40N")
      (description "Resistor - 1%")
      (fields
        (field (name "PART NUMBER") "R0402_1K_1%_0.0625W_100PPM")
        (field (name "POWER") "0.0625W")
        (field (name "AUTHOR") "CERN DEM JLC")
      )
      (libsource (lib "Resistors") (part "Resistor - 1%"))
    )
    (comp (ref "R456")
      (value "3k9")
      (footprint "RESC1005X40N")
      (description "Resistor - 1%")
      (fields
        (field (name "PART NUMBER") "R0402_3K9_1%_0.0625W_100PPM")
        (field (name "POWER") "0.0625W")
        (field (name "AUTHOR") "CERN DEM JLC")
      )
      (libsource (lib "Resistors") (part "Resistor - 1%"))
    )
    (comp (ref "R457")
      (value "0")
      (footprint "RESC1005X40N")
      (description "Resistor")
      (fields
        (field (name "MANUFACTURER PART NUMBER") "R0402_0R_JUMPER")
        (field (name "MANUFACTURER") "GENERIC")
        (field (name "AUTHOR") "CERN DEM JLC")
      )
      (libsource (lib "Resistors") (part "Resistor"))
    )
    (comp (ref "R458")
      (value "0")
      (footprint "RESC1005X40N")
      (description "Resistor")
      (fields
        (field (name "MANUFACTURER PART NUMBER") "R0402_0R_JUMPER")
        (field (name "MANUFACTURER") "GENERIC")
        (field (name "AUTHOR") "CERN DEM JLC")
      )
      (libsource (lib "Resistors") (part "Resistor"))
    )
    (comp (ref "R459")
      (value "0")
      (footprint "RESC1005X40N")
      (description "Resistor")
      (fields
        (field (name "MANUFACTURER PART NUMBER") "R0402_0R_JUMPER")
        (field (name "MANUFACTURER") "GENERIC")
        (field (name "AUTHOR") "CERN DEM JLC")
      )
      (libsource (lib "Resistors") (part "Resistor"))
    )
    (comp (ref "R471")
      (value "10k")
      (footprint "RESC1005X40N")
      (description "Resistor - 1%")
      (fields
        (field (name "MANUFACTURER PART NUMBER") "R0402_10K_1%_0.0625W_100PPM")
        (field (name "MANUFACTURER") "GENERIC")
        (field (name "AUTHOR") "CERN DEM JLC")
      )
      (libsource (lib "Resistors") (part "Resistor - 1%"))
    )
    (comp (ref "R472")
      (value "3k3")
      (footprint "RESC1608X55N")
      (description "Resistor - 1%")
      (fields
        (field (name "PART NUMBER") "R0603_3K3_1%_0.1W_100PPM")
        (field (name "POWER") "0.1W")
        (field (name "AUTHOR") "CERN DEM JLC")
      )
      (libsource (lib "Resistors") (part "Resistor - 1%"))
    )
    (comp (ref "R552")
      (value "0")
      (footprint "RESC1005X40N")
      (description "Resistor")
      (fields
        (field (name "MANUFACTURER PART NUMBER") "R0402_0R_JUMPER")
        (field (name "MANUFACTURER") "GENERIC")
        (field (name "AUTHOR") "CERN DEM JLC")
      )
      (libsource (lib "Resistors") (part "Resistor"))
    )
    (comp (ref "R555")
      (value "0")
      (footprint "RESC1005X40N")
      (description "Resistor")
      (fields
        (field (name "MANUFACTURER PART NUMBER") "R0402_0R_JUMPER")
        (field (name "MANUFACTURER") "GENERIC")
        (field (name "AUTHOR") "CERN DEM JLC")
      )
      (libsource (lib "Resistors") (part "Resistor"))
    )
    (comp (ref "SW1")
      (value "Switch")
      (footprint "SW_TYCO_1571983-4")
      (description "4 Ways SPST DIP Switch")
      (fields
        (field (name "PART NUMBER") "SW_TYCO_1571983-4")
        (field (name "MANUFACTURER") "TYCO")
        (field (name "AUTHOR") "CERN DEM JLC")
      )
      (libsource (lib "Eletro-mechanical") (part "SW 4x SPST DIP Switch"))
    )
    (comp (ref "T9")
      (value "BSS138LT1G")
      (footprint "SOT95P240X110-3N")
      (description "N-CHANNEL MOSFET WITH DIODE")
      (fields (field (name "MANUFACTURER") "ON SEMICONDUCTOR") (field (name "AUTHOR") "CERN DEM JLC"))
      (libsource (lib "ICs And Semiconductors") (part "N-MOSFET-D 1G 2S 3D"))
    )
    (comp (ref "T16")
      (value "BSS138LT1G")
      (footprint "SOT95P240X110-3N")
      (description "N-CHANNEL MOSFET WITH DIODE")
      (fields (field (name "MANUFACTURER") "ON SEMICONDUCTOR") (field (name "AUTHOR") "CERN DEM JLC"))
      (libsource (lib "ICs And Semiconductors") (part "N-MOSFET-D 1G 2S 3D"))
    )
    (comp (ref "X1")
      (value "ECS-80-12-30-JGM-TR")
      (footprint "ECS-80-12-30-JGM-TR")
      (description "Crystal")
      (fields (field (name "MANUFACTURER") "ECS Incorporated") (field (name "FREQUENCY") "8MHz"))
      (libsource (lib "ECS-80-12-30-JGM-TR") (part "ECS-80-12-30-JGM-TR"))
    )
  )
  (nets
    (net (code "10") (name "/1V5_VTT_EN") (class "Default")
      (node (ref "IC66") (pin "13") (pinfunction "GP1.7_13") (pintype "bidirectional"))
    )
    (net (code "11") (name "/AMC_En") (class "Default")
      (node (ref "D6") (pin "1") (pinfunction "C_1") (pintype "passive"))
      (node (ref "R34") (pin "1") (pinfunction "1_1") (pintype "passive"))
      (node (ref "R96") (pin "1") (pinfunction "1_1") (pintype "passive"))
      (node (ref "T16") (pin "3") (pinfunction "D_3") (pintype "passive"))
      (node (ref "T9") (pin "1") (pinfunction "G_1") (pintype "passive"))
    )
    (net (code "12") (name "/AMC_RTM_CRITICAL") (class "Default")
      (node (ref "IC1") (pin "40") (pinfunction "P1[26]/MCOB1/PWM1[6]/CAP0[0]_40") (pintype "bidirectional"))
    )
    (net (code "13") (name "/AMC_RTM_PV") (class "Default")
      (node (ref "IC1") (pin "43") (pinfunction "P1[27]/CLKOUT/~{USB_OVRCR}/CAP0[1]_43") (pintype "bidirectional"))
    )
    (net (code "14") (name "/AMC_RTM_TC") (class "Default")
      (node (ref "IC1") (pin "44") (pinfunction "P1[28]/MCOA2/PCAP1[0]/MAT0[0]_44") (pintype "bidirectional"))
    )
    (net (code "15") (name "/AMC_RTM_WARNING") (class "Default")
      (node (ref "IC1") (pin "45") (pinfunction "P1[29]/MCOB2/PCAP1[1]/MAT0[1]_45") (pintype "bidirectional"))
    )
    (net (code "16") (name "/CLK_DIR_FMC1") (class "Default")
      (node (ref "IC1") (pin "78") (pinfunction "P0[7]/I2STX_CLK/SCK1/MAT2[1]_78") (pintype "bidirectional"))
      (node (ref "R403") (pin "1") (pinfunction "1_1") (pintype "passive"))
    )
    (net (code "17") (name "/CLK_DIR_FMC2") (class "Default")
      (node (ref "IC1") (pin "79") (pinfunction "P0[6]/I2SRX_SDA/SSEL1/MAT2[0]_79") (pintype "bidirectional"))
      (node (ref "R406") (pin "1") (pinfunction "1_1") (pintype "passive"))
    )
    (net (code "18") (name "/CPU_SCL") (class "Default")
      (node (ref "IC1") (pin "47") (pinfunction "P0[1]/TD1/RXD3/SCL1_47") (pintype "bidirectional"))
    )
    (net (code "19") (name "/CPU_SDA") (class "Default")
      (node (ref "IC1") (pin "46") (pinfunction "P0[0]/RD1/TXD3/SDA1_46") (pintype "bidirectional"))
    )
    (net (code "20") (name "/DAC_VADJ_CLK") (class "Default")
      (node (ref "IC1") (pin "62") (pinfunction "P0[15]/TXD1/SCK0/SCK_62") (pintype "bidirectional"))
    )
    (net (code "21") (name "/DAC_VADJ_CSn") (class "Default")
      (node (ref "IC1") (pin "63") (pinfunction "P0[16]/RXD1/SSEL0/SSEL_63") (pintype "bidirectional"))
    )
    (net (code "22") (name "/DAC_VADJ_RSTn") (class "Default")
      (node (ref "IC66") (pin "22") (pinfunction "GP0.1_22") (pintype "bidirectional"))
    )
    (net (code "23") (name "/DAC_VADJ_SDI") (class "Default")
      (node (ref "IC1") (pin "60") (pinfunction "P0[18]/DCD1/MOSI0/MOSI_60") (pintype "bidirectional"))
    )
    (net (code "24") (name "/DONE") (class "Default")
      (node (ref "R153") (pin "2") (pinfunction "2_2") (pintype "passive"))
    )
    (net (code "25") (name "/DONE_L") (class "Default")
      (node (ref "IC1") (pin "56") (pinfunction "P0[22]/RTS1/TD1_56") (pintype "bidirectional"))
      (node (ref "R153") (pin "1") (pinfunction "1_1") (pintype "passive"))
    )
    (net (code "26") (name "/DTR") (class "Default")
      (node (ref "IC45") (pin "1") (pinfunction "A_1") (pintype "input"))
      (node (ref "J17") (pin "3") (pinfunction "3_3") (pintype "passive"))
      (node (ref "R446") (pin "2") (pinfunction "2_2") (pintype "passive"))
      (node (ref "SW1") (pin "1") (pinfunction "1_1") (pintype "bidirectional"))
    )
    (net (code "27") (name "/EEPROM_WP") (class "Default")
      (node (ref "IC1") (pin "21") (pinfunction "P1[30]/VBUS/AD0[4]_21") (pintype "bidirectional"))
    )
    (net (code "28") (name "/ENABLE#_L") (class "Default")
      (node (ref "IC1") (pin "65") (pinfunction "P2[8]/TD2/TXD2_65") (pintype "bidirectional"))
      (node (ref "R96") (pin "2") (pinfunction "2_2") (pintype "passive"))
    )
    (net (code "29") (name "/EN_FMC1_P3V3") (class "Default")
      (node (ref "IC66") (pin "2") (pinfunction "GP1.0_2") (pintype "bidirectional"))
    )
    (net (code "30") (name "/EN_FMC1_P12V") (class "Default")
      (node (ref "IC66") (pin "7") (pinfunction "GP1.4_7") (pintype "bidirectional"))
    )
    (net (code "31") (name "/EN_FMC1_PVADJ") (class "Default")
      (node (ref "IC66") (pin "4") (pinfunction "GP1.2_4") (pintype "bidirectional"))
    )
    (net (code "32") (name "/EN_FMC2_P3V3") (class "Default")
      (node (ref "IC66") (pin "28") (pinfunction "GP0.7_28") (pintype "bidirectional"))
    )
    (net (code "33") (name "/EN_FMC2_P12V") (class "Default")
      (node (ref "IC66") (pin "5") (pinfunction "GP1.3_5") (pintype "bidirectional"))
    )
    (net (code "34") (name "/EN_FMC2_PVADJ") (class "Default")
      (node (ref "IC66") (pin "3") (pinfunction "GP1.1_3") (pintype "bidirectional"))
    )
    (net (code "35") (name "/EN_P1V0") (class "Default")
      (node (ref "IC66") (pin "27") (pinfunction "GP0.6_27") (pintype "bidirectional"))
    )
    (net (code "36") (name "/EN_P1V2") (class "Default")
      (node (ref "IC66") (pin "11") (pinfunction "GP1.5_11") (pintype "bidirectional"))
    )
    (net (code "37") (name "/EN_P1V8") (class "Default")
      (node (ref "IC66") (pin "12") (pinfunction "GP1.6_12") (pintype "bidirectional"))
    )
    (net (code "38") (name "/EN_P3V3") (class "Default")
      (node (ref "IC66") (pin "26") (pinfunction "GP0.5_26") (pintype "bidirectional"))
    )
    (net (code "39") (name "/EN_RTM_MP") (class "Default")
      (node (ref "IC66") (pin "24") (pinfunction "GP0.3_24") (pintype "bidirectional"))
    )
    (net (code "40") (name "/EN_RTM_PWR") (class "Default")
      (node (ref "IC66") (pin "25") (pinfunction "GP0.4_25") (pintype "bidirectional"))
    )
    (net (code "44") (name "/FMC1_CRITICAL") (class "Default")
      (node (ref "IC1") (pin "9") (pinfunction "P0[23]/AD0[0]/I2SRX_CLK/CAP3[0]_9") (pintype "bidirectional"))
    )
    (net (code "45") (name "/FMC1_JTAG_Override") (class "Default")
      (node (ref "IC1") (pin "74") (pinfunction "P2[1]/PWM1[2]/RXD1_74") (pintype "bidirectional"))
    )
    (net (code "46") (name "/FMC1_PG_C2M") (class "Default")
      (node (ref "R17") (pin "1") (pinfunction "1_1") (pintype "passive"))
      (node (ref "R98") (pin "1") (pinfunction "1_1") (pintype "passive"))
    )
    (net (code "47") (name "/FMC1_PG_C2M_R") (class "Default")
      (node (ref "IC1") (pin "32") (pinfunction "P1[18]/USB_UP_LED/PWM1[1]/CAP1[0]_32") (pintype "bidirectional"))
      (node (ref "R17") (pin "2") (pinfunction "2_2") (pintype "passive"))
    )
    (net (code "48") (name "/FMC1_PG_M2C") (class "Default")
      (node (ref "R100") (pin "1") (pinfunction "1_1") (pintype "passive"))
      (node (ref "R15") (pin "1") (pinfunction "1_1") (pintype "passive"))
    )
    (net (code "49") (name "/FMC1_PG_M2C_R") (class "Default")
      (node (ref "IC1") (pin "87") (pinfunction "P1[16]/ENET_MDC_87") (pintype "bidirectional"))
      (node (ref "R15") (pin "2") (pinfunction "2_2") (pintype "passive"))
    )
    (net (code "50") (name "/FMC1_PRSNT_M2C_L") (class "Default")
      (node (ref "R102") (pin "1") (pinfunction "1_1") (pintype "passive"))
      (node (ref "R13") (pin "1") (pinfunction "1_1") (pintype "passive"))
    )
    (net (code "51") (name "/FMC1_PRSNT_M2C__R") (class "Default")
      (node (ref "IC1") (pin "89") (pinfunction "P1[14]/ENET_RX_ER_89") (pintype "bidirectional"))
      (node (ref "R13") (pin "2") (pinfunction "2_2") (pintype "passive"))
    )
    (net (code "52") (name "/FMC1_PV") (class "Default")
      (node (ref "IC1") (pin "20") (pinfunction "P1[31]/SCK1/AD0[5]_20") (pintype "bidirectional"))
    )
    (net (code "53") (name "/FMC1_TC") (class "Default")
      (node (ref "IC1") (pin "7") (pinfunction "P0[25]/AD0[2]/I2SRX_SDA/TXD3_7") (pintype "bidirectional"))
    )
    (net (code "54") (name "/FMC1_WARNING") (class "Default")
      (node (ref "IC1") (pin "6") (pinfunction "P0[26]/AD0[3]/AOUT/RXD3_6") (pintype "bidirectional"))
    )
    (net (code "55") (name "/FMC2_CRITICAL") (class "Default")
      (node (ref "IC1") (pin "66") (pinfunction "P2[7]/RD2/RTS1_66") (pintype "bidirectional"))
    )
    (net (code "56") (name "/FMC2_JTAG_Override") (class "Default")
      (node (ref "IC1") (pin "77") (pinfunction "P0[8]/I2STX_WS/MISO1/MAT2[2]_77") (pintype "bidirectional"))
    )
    (net (code "57") (name "/FMC2_PG_C2M") (class "Default")
      (node (ref "R18") (pin "1") (pinfunction "1_1") (pintype "passive"))
      (node (ref "R97") (pin "1") (pinfunction "1_1") (pintype "passive"))
    )
    (net (code "58") (name "/FMC2_PG_C2M_R") (class "Default")
      (node (ref "IC1") (pin "33") (pinfunction "P1[19]/MCOA0/~{USB_PPWR}/CAP1[1]_33") (pintype "bidirectional"))
      (node (ref "R18") (pin "2") (pinfunction "2_2") (pintype "passive"))
    )
    (net (code "59") (name "/FMC2_PG_M2C") (class "Default")
      (node (ref "R16") (pin "1") (pinfunction "1_1") (pintype "passive"))
      (node (ref "R99") (pin "1") (pinfunction "1_1") (pintype "passive"))
    )
    (net (code "60") (name "/FMC2_PG_M2C_R") (class "Default")
      (node (ref "IC1") (pin "86") (pinfunction "P1[17]/ENET_MDIO_86") (pintype "bidirectional"))
      (node (ref "R16") (pin "2") (pinfunction "2_2") (pintype "passive"))
    )
    (net (code "61") (name "/FMC2_PRSNT_M2C_L") (class "Default")
      (node (ref "R101") (pin "1") (pinfunction "1_1") (pintype "passive"))
      (node (ref "R14") (pin "1") (pinfunction "1_1") (pintype "passive"))
    )
    (net (code "62") (name "/FMC2_PRSNT_M2C__R") (class "Default")
      (node (ref "IC1") (pin "88") (pinfunction "P1[15]/ENET_REF_CLK_88") (pintype "bidirectional"))
      (node (ref "R14") (pin "2") (pinfunction "2_2") (pintype "passive"))
    )
    (net (code "63") (name "/FMC2_PV") (class "Default")
      (node (ref "IC1") (pin "27") (pinfunction "P3[25]/MAT0[0]/PWM1[2]_27") (pintype "bidirectional"))
    )
    (net (code "64") (name "/FMC2_TC") (class "Default")
      (node (ref "IC1") (pin "82") (pinfunction "P4[28]/RX_MCLK/MAT2[0]/TXD3_82") (pintype "bidirectional"))
    )
    (net (code "65") (name "/FMC2_WARNING") (class "Default")
      (node (ref "IC1") (pin "85") (pinfunction "P4[29]/TX_MCLK/MAT2[1]/RXD3_85") (pintype "bidirectional"))
    )
    (net (code "67") (name "/FPGA_I2C_RESET") (class "Default")
      (node (ref "IC66") (pin "23") (pinfunction "GP0.2_23") (pintype "bidirectional"))
    )
    (net (code "68") (name "/FPGA_RESETn") (class "Default")
      (node (ref "IC1") (pin "64") (pinfunction "P2[9]/USB_CONNECT/RXD2_64") (pintype "bidirectional"))
    )
    (net (code "69") (name "/GA0") (class "Default")
      (node (ref "IC5") (pin "4") (pinfunction "C3_4") (pintype "passive"))
      (node (ref "R20") (pin "1") (pinfunction "1_1") (pintype "passive"))
      (node (ref "R7") (pin "1") (pinfunction "1_1") (pintype "passive"))
    )
    (net (code "70") (name "/GA0_R") (class "Default")
      (node (ref "IC1") (pin "95") (pinfunction "P1[0]/ENET_TXD0_95") (pintype "bidirectional"))
      (node (ref "R7") (pin "2") (pinfunction "2_2") (pintype "passive"))
    )
    (net (code "71") (name "/GA1") (class "Default")
      (node (ref "IC5") (pin "3") (pinfunction "C2_3") (pintype "passive"))
      (node (ref "R21") (pin "1") (pinfunction "1_1") (pintype "passive"))
      (node (ref "R8") (pin "1") (pinfunction "1_1") (pintype "passive"))
    )
    (net (code "72") (name "/GA1_R") (class "Default")
      (node (ref "IC1") (pin "94") (pinfunction "P1[1]/ENET_TXD1_94") (pintype "bidirectional"))
      (node (ref "R8") (pin "2") (pinfunction "2_2") (pintype "passive"))
    )
    (net (code "73") (name "/GA2") (class "Default")
      (node (ref "IC5") (pin "1") (pinfunction "C1_1") (pintype "passive"))
      (node (ref "R22") (pin "1") (pinfunction "1_1") (pintype "passive"))
      (node (ref "R9") (pin "1") (pinfunction "1_1") (pintype "passive"))
    )
    (net (code "74") (name "/GA2_R") (class "Default")
      (node (ref "IC1") (pin "93") (pinfunction "P1[4]/ENET_TX_EN_93") (pintype "bidirectional"))
      (node (ref "R9") (pin "2") (pinfunction "2_2") (pintype "passive"))
    )
    (net (code "75") (name "/I2C_MUX_ADDR1") (class "Default")
      (node (ref "IC1") (pin "81") (pinfunction "P0[4]/I2SRX_CLK/RD2/CAP2[0]_81") (pintype "bidirectional"))
    )
    (net (code "76") (name "/I2C_MUX_ADDR2") (class "Default")
      (node (ref "IC1") (pin "80") (pinfunction "P0[5]/I2SRX_WS/TD2/CAP2[1]_80") (pintype "bidirectional"))
    )
    (net (code "78") (name "/I2C_SW_RESETn") (class "Default")
      (node (ref "IC1") (pin "59") (pinfunction "P0[19]/DSR1/SDA1_59") (pintype "bidirectional"))
      (node (ref "R121") (pin "2") (pinfunction "2_2") (pintype "passive"))
    )
    (net (code "79") (name "/INIT_B") (class "Default")
      (node (ref "R346") (pin "1") (pinfunction "1_1") (pintype "passive"))
    )
    (net (code "80") (name "/MCP_SCL") (class "Default")
      (node (ref "IC1") (pin "49") (pinfunction "P0[11]/RXD2/SCL2/MAT3[1]_49") (pintype "bidirectional"))
      (node (ref "IC66") (pin "14") (pinfunction "SCL_14") (pintype "input"))
      (node (ref "R125") (pin "1") (pinfunction "1_1") (pintype "passive"))
    )
    (net (code "81") (name "/MCP_SDA") (class "Default")
      (node (ref "IC1") (pin "48") (pinfunction "P0[10]/TXD2/SDA2/MAT3[0]_48") (pintype "bidirectional"))
      (node (ref "IC66") (pin "15") (pinfunction "SDA_15") (pintype "bidirectional"))
      (node (ref "R6") (pin "1") (pinfunction "1_1") (pintype "passive"))
    )
    (net (code "82") (name "/MMC_FPGA_MISO") (class "Default")
      (node (ref "IC1") (pin "37") (pinfunction "P1[23]/MCI1/PWM1[4]/MISO0_37") (pintype "bidirectional"))
    )
    (net (code "83") (name "/MMC_FPGA_MOSI") (class "Default")
      (node (ref "IC1") (pin "38") (pinfunction "P1[24]/MCI2/PWM1[5]/MOSI0_38") (pintype "bidirectional"))
    )
    (net (code "84") (name "/MMC_FPGA_SCK") (class "Default")
      (node (ref "IC1") (pin "34") (pinfunction "P1[20]/MCI0/PWM1[2]/SCK0_34") (pintype "bidirectional"))
    )
    (net (code "85") (name "/MMC_FPGA_SSEL") (class "Default")
      (node (ref "IC1") (pin "35") (pinfunction "P1[21]/~{MCABORT}/PWM1[3]/SSEL0_35") (pintype "bidirectional"))
    )
    (net (code "86") (name "/MMC_JTAG_presence") (class "Default")
      (node (ref "J9") (pin "19") (pinfunction "19_19") (pintype "bidirectional"))
    )
    (net (code "87") (name "/MMC_RESETn") (class "Default")
      (node (ref "D5") (pin "1") (pinfunction "C_1") (pintype "passive"))
      (node (ref "IC3") (pin "1") (pinfunction "~{RESET}_1") (pintype "output"))
    )
    (net (code "88") (name "/MMC_TCK") (class "Default")
      (node (ref "R139") (pin "2") (pinfunction "2_2") (pintype "passive"))
    )
    (net (code "89") (name "/MMC_TCK_SW") (class "Default")
      (node (ref "IC1") (pin "5") (pinfunction "TCK/SWDCLK_5") (pintype "input"))
      (node (ref "J9") (pin "4") (pinfunction "4_4") (pintype "bidirectional"))
      (node (ref "R139") (pin "1") (pinfunction "1_1") (pintype "passive"))
      (node (ref "R5") (pin "2") (pinfunction "2_2") (pintype "passive"))
    )
    (net (code "90") (name "/MMC_TDI") (class "Default")
      (node (ref "R118") (pin "2") (pinfunction "2_2") (pintype "passive"))
    )
    (net (code "91") (name "/MMC_TDI_SW") (class "Default")
      (node (ref "IC1") (pin "2") (pinfunction "TDI_2") (pintype "input"))
      (node (ref "J9") (pin "8") (pinfunction "8_8") (pintype "bidirectional"))
      (node (ref "R118") (pin "1") (pinfunction "1_1") (pintype "passive"))
    )
    (net (code "92") (name "/MMC_TDO") (class "Default")
      (node (ref "R60") (pin "2") (pinfunction "2_2") (pintype "passive"))
    )
    (net (code "93") (name "/MMC_TDO_SW") (class "Default")
      (node (ref "IC1") (pin "1") (pinfunction "TDO/SWO_1") (pintype "output"))
      (node (ref "J9") (pin "6") (pinfunction "6_6") (pintype "bidirectional"))
      (node (ref "R60") (pin "1") (pinfunction "1_1") (pintype "passive"))
    )
    (net (code "94") (name "/MMC_TMS") (class "Default")
      (node (ref "R56") (pin "2") (pinfunction "2_2") (pintype "passive"))
    )
    (net (code "95") (name "/MMC_TMS_SW") (class "Default")
      (node (ref "IC1") (pin "3") (pinfunction "TMS/SWDIO_3") (pintype "bidirectional"))
      (node (ref "J9") (pin "2") (pinfunction "2_2") (pintype "bidirectional"))
      (node (ref "R4") (pin "1") (pinfunction "1_1") (pintype "passive"))
      (node (ref "R56") (pin "1") (pinfunction "1_1") (pintype "passive"))
    )
    (net (code "96") (name "/MMC_TRSTn") (class "Default")
      (node (ref "R1") (pin "2") (pinfunction "2_2") (pintype "passive"))
    )
    (net (code "97") (name "/MMC_TRSTn_SW") (class "Default")
      (node (ref "IC1") (pin "4") (pinfunction "~{TRST}_4") (pintype "input"))
      (node (ref "R1") (pin "1") (pinfunction "1_1") (pintype "passive"))
      (node (ref "R3") (pin "1") (pinfunction "1_1") (pintype "passive"))
    )
    (net (code "98") (name "/MOD_HANDLE") (class "Default")
      (node (ref "IC1") (pin "50") (pinfunction "P2[13]/~{EINT3}/I2STX_SDA_50") (pintype "bidirectional"))
      (node (ref "PB1") (pin "1") (pinfunction "1_1") (pintype "passive"))
      (node (ref "PB1") (pin "2") (pinfunction "2_2") (pintype "passive"))
      (node (ref "R19") (pin "1") (pinfunction "1_1") (pintype "passive"))
    )
    (net (code "99") (name "/MP_XTAL1") (class "Default")
      (node (ref "C18") (pin "2") (pinfunction "2_2") (pintype "passive"))
      (node (ref "IC1") (pin "22") (pinfunction "XTAL1_22") (pintype "passive"))
      (node (ref "X1") (pin "1") (pinfunction "1_1") (pintype "passive"))
    )
    (net (code "100") (name "/MP_XTAL2") (class "Default")
      (node (ref "C19") (pin "2") (pinfunction "2_2") (pintype "passive"))
      (node (ref "IC1") (pin "23") (pinfunction "XTAL2_23") (pintype "passive"))
      (node (ref "X1") (pin "2") (pinfunction "2_2") (pintype "passive"))
    )
    (net (code "101") (name "/MRn") (class "Default")
      (node (ref "IC3") (pin "3") (pinfunction "~{MR}_3") (pintype "input"))
      (node (ref "R33") (pin "1") (pinfunction "1_1") (pintype "passive"))
      (node (ref "R35") (pin "1") (pinfunction "1_1") (pintype "passive"))
    )
    (net (code "102") (name "/MRnR") (class "Default")
      (node (ref "R35") (pin "2") (pinfunction "2_2") (pintype "passive"))
      (node (ref "T9") (pin "3") (pinfunction "D_3") (pintype "passive"))
    )
    (net (code "103") (name "/OVERTEMPn") (class "Default")
      (node (ref "IC1") (pin "52") (pinfunction "P2[11]/~{EINT1}/I2STX_CLK_52") (pintype "bidirectional"))
    )
    (net (code "104") (name "/P1") (class "Default")
      (node (ref "R10") (pin "1") (pinfunction "1_1") (pintype "passive"))
      (node (ref "R20") (pin "2") (pinfunction "2_2") (pintype "passive"))
      (node (ref "R21") (pin "2") (pinfunction "2_2") (pintype "passive"))
      (node (ref "R22") (pin "2") (pinfunction "2_2") (pintype "passive"))
    )
    (net (code "105") (name "/P1_R") (class "Default")
      (node (ref "IC1") (pin "92") (pinfunction "P1[8]/ENET_CRS_92") (pintype "bidirectional"))
      (node (ref "R10") (pin "2") (pinfunction "2_2") (pintype "passive"))
    )
    (net (code "106") (name "/P2") (class "Default")
      (node (ref "R11") (pin "1") (pinfunction "1_1") (pintype "passive"))
      (node (ref "R23") (pin "1") (pinfunction "1_1") (pintype "passive"))
    )
    (net (code "107") (name "/P2_BLUE") (class "Default")
      (node (ref "LED1") (pin "2") (pinfunction "C_2") (pintype "passive"))
      (node (ref "R23") (pin "2") (pinfunction "2_2") (pintype "passive"))
    )
    (net (code "108") (name "/P2_R") (class "Default")
      (node (ref "IC1") (pin "91") (pinfunction "P1[9]/ENET_RXD0_91") (pintype "bidirectional"))
      (node (ref "R11") (pin "2") (pinfunction "2_2") (pintype "passive"))
    )
    (net (code "109") (name "/P3") (class "Default")
      (node (ref "R12") (pin "1") (pinfunction "1_1") (pintype "passive"))
      (node (ref "R24") (pin "1") (pinfunction "1_1") (pintype "passive"))
    )
    (net (code "110") (name "/P3V3MP_LAVCC") (class "Default")
      (node (ref "C28") (pin "1") (pinfunction "1_1") (pintype "passive"))
      (node (ref "FB1") (pin "1") (pinfunction "1_1") (pintype "passive"))
      (node (ref "IC1") (pin "10") (pinfunction "VDDA_10") (pintype "power_in"))
      (node (ref "IC1") (pin "12") (pinfunction "VREFP_12") (pintype "power_in"))
    )
    (net (code "111") (name "/P3_GREEN") (class "Default")
      (node (ref "LED2") (pin "2") (pinfunction "C_2") (pintype "passive"))
      (node (ref "R24") (pin "2") (pinfunction "2_2") (pintype "passive"))
    )
    (net (code "112") (name "/P3_R") (class "Default")
      (node (ref "IC1") (pin "90") (pinfunction "P1[10]/ENET_RXD1_90") (pintype "bidirectional"))
      (node (ref "R12") (pin "2") (pinfunction "2_2") (pintype "passive"))
    )
    (net (code "113") (name "/P4") (class "Default")
      (node (ref "IC1") (pin "39") (pinfunction "P1[25]/MCOA1/MAT1[1]_39") (pintype "bidirectional"))
      (node (ref "R175") (pin "1") (pinfunction "1_1") (pintype "passive"))
    )
    (net (code "114") (name "/P4_RED") (class "Default")
      (node (ref "LED17") (pin "1") (pinfunction "C_1") (pintype "passive"))
      (node (ref "R175") (pin "2") (pinfunction "2_2") (pintype "passive"))
    )
    (net (code "115") (name "/PGOOD_P1V0") (class "Default")
      (node (ref "IC1") (pin "26") (pinfunction "P3[26]/STCLK/MAT0[1]/PWM1[3]_26") (pintype "bidirectional"))
    )
    (net (code "116") (name "/PROGRAM_B") (class "Default")
      (node (ref "R152") (pin "1") (pinfunction "1_1") (pintype "passive"))
    )
    (net (code "118") (name "/PROG_RxD") (class "Default")
      (node (ref "IC1") (pin "99") (pinfunction "P0[3]/RXD0/AD0[6]_99") (pintype "bidirectional"))
      (node (ref "J17") (pin "9") (pinfunction "9_9") (pintype "passive"))
    )
    (net (code "119") (name "/PROG_TxD") (class "Default")
      (node (ref "IC1") (pin "98") (pinfunction "P0[2]/TXD0/AD0[7]_98") (pintype "bidirectional"))
      (node (ref "J17") (pin "7") (pinfunction "7_7") (pintype "passive"))
    )
    (net (code "120") (name "/RESETn") (class "Default")
      (node (ref "IC1") (pin "36") (pinfunction "P1[22]/MCOB0/USB_PWRD/MAT1[0]_36") (pintype "bidirectional"))
    )
    (net (code "121") (name "/RST") (class "Default")
      (node (ref "C306") (pin "1") (pinfunction "1_1") (pintype "passive"))
      (node (ref "D33") (pin "2") (pinfunction "A_2") (pintype "passive"))
      (node (ref "D5") (pin "2") (pinfunction "A_2") (pintype "passive"))
      (node (ref "IC1") (pin "17") (pinfunction "~{RESET}_17") (pintype "input"))
      (node (ref "J9") (pin "10") (pinfunction "10_10") (pintype "bidirectional"))
      (node (ref "R2") (pin "1") (pinfunction "1_1") (pintype "passive"))
      (node (ref "R555") (pin "2") (pinfunction "2_2") (pintype "passive"))
      (node (ref "SW1") (pin "5") (pinfunction "5_5") (pintype "bidirectional"))
    )
    (net (code "122") (name "/RTM_JTAG_Override") (class "Default")
      (node (ref "IC1") (pin "75") (pinfunction "P2[0]/PWM1[1]/TXD1_75") (pintype "bidirectional"))
    )
    (net (code "123") (name "/RTM_PS#") (class "Default")
      (node (ref "D1") (pin "1") (pinfunction "C_1") (pintype "passive"))
      (node (ref "R31") (pin "1") (pinfunction "1_1") (pintype "passive"))
      (node (ref "R32") (pin "2") (pinfunction "2_2") (pintype "passive"))
    )
    (net (code "124") (name "/RTS") (class "Default")
      (node (ref "IC45") (pin "2") (pinfunction "B_2") (pintype "input"))
      (node (ref "J17") (pin "5") (pinfunction "5_5") (pintype "passive"))
      (node (ref "R441") (pin "2") (pinfunction "2_2") (pintype "passive"))
      (node (ref "R552") (pin "1") (pinfunction "1_1") (pintype "passive"))
      (node (ref "SW1") (pin "3") (pinfunction "3_3") (pintype "bidirectional"))
    )
    (net (code "125") (name "/RTSa") (class "Default")
      (node (ref "IC1") (pin "53") (pinfunction "P2[10]/~{EINT0}/NMI_53") (pintype "bidirectional"))
      (node (ref "R552") (pin "2") (pinfunction "2_2") (pintype "passive"))
      (node (ref "SW1") (pin "6") (pinfunction "6_6") (pintype "bidirectional"))
    )
    (net (code "126") (name "/SCL0") (class "Default")
      (node (ref "IC1") (pin "24") (pinfunction "P0[28]/SCL0/USB_SCL_24") (pintype "bidirectional"))
      (node (ref "IC4") (pin "4") (pinfunction "C3_4") (pintype "passive"))
      (node (ref "R47") (pin "2") (pinfunction "2_2") (pintype "passive"))
    )
    (net (code "127") (name "/SDA0") (class "Default")
      (node (ref "IC1") (pin "25") (pinfunction "P0[27]/SDA0/USB_SDA_25") (pintype "bidirectional"))
      (node (ref "IC4") (pin "6") (pinfunction "C4_6") (pintype "passive"))
      (node (ref "R169") (pin "2") (pinfunction "2_2") (pintype "passive"))
    )
    (net (code "128") (name "/SW") (class "Default")
      (node (ref "IC1") (pin "51") (pinfunction "P2[12]/~{EINT2}/I2STX_WS_51") (pintype "bidirectional"))
      (node (ref "PB2") (pin "1") (pinfunction "1_1") (pintype "bidirectional"))
      (node (ref "R238") (pin "1") (pinfunction "1_1") (pintype "passive"))
    )
    (net (code "129") (name "/TRACECLK") (class "Default")
      (node (ref "IC1") (pin "67") (pinfunction "P2[6]/PCAP1[0]/RI1/TRACECLK_67") (pintype "bidirectional"))
      (node (ref "J9") (pin "12") (pinfunction "12_12") (pintype "bidirectional"))
    )
    (net (code "130") (name "/TRACEDATA0") (class "Default")
      (node (ref "IC1") (pin "68") (pinfunction "P2[5]/PWM1[6]/DTR1/TRACEDATA[0]_68") (pintype "bidirectional"))
      (node (ref "J9") (pin "14") (pinfunction "14_14") (pintype "bidirectional"))
    )
    (net (code "131") (name "/TRACEDATA1") (class "Default")
      (node (ref "IC1") (pin "69") (pinfunction "P2[4]/PWM1[5]/DSR1/TRACEDATA[1]_69") (pintype "bidirectional"))
      (node (ref "J9") (pin "16") (pinfunction "16_16") (pintype "bidirectional"))
    )
    (net (code "132") (name "/TRACEDATA2") (class "Default")
      (node (ref "IC1") (pin "70") (pinfunction "P2[3]/PWM1[4]/DCD1/TRACEDATA[2]_70") (pintype "bidirectional"))
      (node (ref "J9") (pin "18") (pinfunction "18_18") (pintype "bidirectional"))
    )
    (net (code "133") (name "/TRACEDATA3") (class "Default")
      (node (ref "IC1") (pin "73") (pinfunction "P2[2]/PWM1[3]/CTS1/TRACEDATA[3]_73") (pintype "bidirectional"))
      (node (ref "J9") (pin "20") (pinfunction "20_20") (pintype "bidirectional"))
    )
    (net (code "143") (name "GND") (class "Default")
      (node (ref "C18") (pin "1") (pinfunction "1_1") (pintype "passive"))
      (node (ref "C19") (pin "1") (pinfunction "1_1") (pintype "passive"))
      (node (ref "C21") (pin "1") (pinfunction "1_1") (pintype "passive"))
      (node (ref "C22") (pin "1") (pinfunction "1_1") (pintype "passive"))
      (node (ref "C23") (pin "1") (pinfunction "1_1") (pintype "passive"))
      (node (ref "C24") (pin "1") (pinfunction "1_1") (pintype "passive"))
      (node (ref "C25") (pin "1") (pinfunction "1_1") (pintype "passive"))
      (node (ref "C26") (pin "1") (pinfunction "1_1") (pintype "passive"))
      (node (ref "C27") (pin "1") (pinfunction "1_1") (pintype "passive"))
      (node (ref "C28") (pin "2") (pinfunction "2_2") (pintype "passive"))
      (node (ref "C306") (pin "2") (pinfunction "2_2") (pintype "passive"))
      (node (ref "C406") (pin "1") (pinfunction "1_1") (pintype "passive"))
      (node (ref "C452") (pin "2") (pinfunction "2_2") (pintype "passive"))
      (node (ref "C453") (pin "1") (pinfunction "1_1") (pintype "passive"))
      (node (ref "C496") (pin "2") (pinfunction "2_2") (pintype "passive"))
      (node (ref "D1") (pin "2") (pinfunction "A_2") (pintype "passive"))
      (node (ref "D6") (pin "2") (pinfunction "A_2") (pintype "passive"))
      (node (ref "IC1") (pin "11") (pinfunction "VSSA_11") (pintype "power_in"))
      (node (ref "IC1") (pin "15") (pinfunction "VREFN_15") (pintype "power_in"))
      (node (ref "IC1") (pin "31") (pinfunction "VSS_31") (pintype "power_in"))
      (node (ref "IC1") (pin "41") (pinfunction "VSS_41") (pintype "power_in"))
      (node (ref "IC1") (pin "55") (pinfunction "VSS_55") (pintype "power_in"))
      (node (ref "IC1") (pin "72") (pinfunction "VSS_72") (pintype "power_in"))
      (node (ref "IC1") (pin "83") (pinfunction "VSS_83") (pintype "power_in"))
      (node (ref "IC1") (pin "97") (pinfunction "VSS_97") (pintype "power_in"))
      (node (ref "IC3") (pin "2") (pinfunction "GND_2") (pintype "power_in"))
      (node (ref "IC4") (pin "2") (pinfunction "A_2") (pintype "passive"))
      (node (ref "IC4") (pin "5") (pinfunction "A_5") (pintype "passive"))
      (node (ref "IC45") (pin "3") (pinfunction "GND_3") (pintype "power_in"))
      (node (ref "IC5") (pin "2") (pinfunction "A_2") (pintype "passive"))
      (node (ref "IC5") (pin "5") (pinfunction "A_5") (pintype "passive"))
      (node (ref "IC66") (pin "1") (pinfunction "VSS_1") (pintype "power_in"))
      (node (ref "IC66") (pin "19") (pinfunction "VSS_19") (pintype "power_in"))
      (node (ref "IC66") (pin "8") (pinfunction "VSS_8") (pintype "power_in"))
      (node (ref "J17") (pin "10") (pinfunction "10_10") (pintype "passive"))
      (node (ref "J17") (pin "4") (pinfunction "4_4") (pintype "passive"))
      (node (ref "J17") (pin "6") (pinfunction "6_6") (pintype "passive"))
      (node (ref "J17") (pin "8") (pinfunction "8_8") (pintype "passive"))
      (node (ref "J9") (pin "11") (pinfunction "11_11") (pintype "bidirectional"))
      (node (ref "J9") (pin "13") (pinfunction "13_13") (pintype "bidirectional"))
      (node (ref "J9") (pin "15") (pinfunction "15_15") (pintype "bidirectional"))
      (node (ref "J9") (pin "17") (pinfunction "17_17") (pintype "bidirectional"))
      (node (ref "J9") (pin "3") (pinfunction "3_3") (pintype "bidirectional"))
      (node (ref "J9") (pin "5") (pinfunction "5_5") (pintype "bidirectional"))
      (node (ref "J9") (pin "9") (pinfunction "9_9") (pintype "bidirectional"))
      (node (ref "PB1") (pin "3") (pinfunction "3_3") (pintype "passive"))
      (node (ref "PB1") (pin "4") (pinfunction "4_4") (pintype "passive"))
      (node (ref "PB2") (pin "2") (pinfunction "2_2") (pintype "bidirectional"))
      (node (ref "PB2") (pin "3") (pinfunction "3_3") (pintype "passive"))
      (node (ref "PB2") (pin "4") (pinfunction "4_4") (pintype "passive"))
      (node (ref "R127") (pin "1") (pinfunction "1_1") (pintype "passive"))
      (node (ref "R403") (pin "2") (pinfunction "2_2") (pintype "passive"))
      (node (ref "R406") (pin "2") (pinfunction "2_2") (pintype "passive"))
      (node (ref "R441") (pin "1") (pinfunction "1_1") (pintype "passive"))
      (node (ref "R446") (pin "1") (pinfunction "1_1") (pintype "passive"))
      (node (ref "R457") (pin "1") (pinfunction "1_1") (pintype "passive"))
      (node (ref "R458") (pin "1") (pinfunction "1_1") (pintype "passive"))
      (node (ref "R459") (pin "1") (pinfunction "1_1") (pintype "passive"))
      (node (ref "R472") (pin "1") (pinfunction "1_1") (pintype "passive"))
      (node (ref "R5") (pin "1") (pinfunction "1_1") (pintype "passive"))
      (node (ref "T16") (pin "2") (pinfunction "S_2") (pintype "passive"))
      (node (ref "T9") (pin "2") (pinfunction "S_2") (pintype "passive"))
    )
    (net (code "144") (name "Net-(D33-C)") (class "Default")
      (node (ref "D33") (pin "1") (pinfunction "C_1") (pintype "passive"))
      (node (ref "SW1") (pin "8") (pinfunction "8_8") (pintype "bidirectional"))
    )
    (net (code "145") (name "Net-(IC1A-P0[20]{slash}DTR1{slash}SCL1)") (class "Default")
      (node (ref "IC1") (pin "58") (pinfunction "P0[20]/DTR1/SCL1_58") (pintype "bidirectional"))
      (node (ref "R346") (pin "2") (pinfunction "2_2") (pintype "passive"))
    )
    (net (code "146") (name "Net-(IC1A-P0[24]{slash}AD0[1]{slash}I2SRX_WS{slash}CAP3[1])") (class "Default")
      (node (ref "IC1") (pin "8") (pinfunction "P0[24]/AD0[1]/I2SRX_WS/CAP3[1]_8") (pintype "bidirectional"))
      (node (ref "R471") (pin "1") (pinfunction "1_1") (pintype "passive"))
      (node (ref "R472") (pin "2") (pinfunction "2_2") (pintype "passive"))
    )
    (net (code "147") (name "Net-(IC1A-P0[29]{slash}USB_D+)") (class "Default")
      (node (ref "IC1") (pin "29") (pinfunction "P0[29]/USB_D+_29") (pintype "bidirectional"))
      (node (ref "R32") (pin "1") (pinfunction "1_1") (pintype "passive"))
    )
    (net (code "148") (name "Net-(IC3-CT)") (class "Default")
      (node (ref "C406") (pin "2") (pinfunction "2_2") (pintype "passive"))
      (node (ref "IC3") (pin "4") (pinfunction "CT_4") (pintype "passive"))
    )
    (net (code "149") (name "Net-(IC45A-Y)") (class "Default")
      (node (ref "IC45") (pin "4") (pinfunction "Y_4") (pintype "output"))
      (node (ref "R437") (pin "1") (pinfunction "1_1") (pintype "passive"))
    )
    (net (code "150") (name "Net-(IC66-A0)") (class "Default")
      (node (ref "IC66") (pin "16") (pinfunction "A0_16") (pintype "input"))
      (node (ref "R459") (pin "2") (pinfunction "2_2") (pintype "passive"))
    )
    (net (code "151") (name "Net-(IC66-A1)") (class "Default")
      (node (ref "IC66") (pin "17") (pinfunction "A1_17") (pintype "input"))
      (node (ref "R458") (pin "2") (pinfunction "2_2") (pintype "passive"))
    )
    (net (code "152") (name "Net-(IC66-A2)") (class "Default")
      (node (ref "IC66") (pin "18") (pinfunction "A2_18") (pintype "input"))
      (node (ref "R457") (pin "2") (pinfunction "2_2") (pintype "passive"))
    )
    (net (code "153") (name "Net-(IC66-CLK)") (class "Default")
      (node (ref "C453") (pin "2") (pinfunction "2_2") (pintype "passive"))
      (node (ref "IC66") (pin "9") (pinfunction "CLK_9") (pintype "input"))
      (node (ref "R456") (pin "1") (pinfunction "1_1") (pintype "passive"))
    )
    (net (code "154") (name "Net-(IC66-GP0.0)") (class "Default")
      (node (ref "IC66") (pin "21") (pinfunction "GP0.0_21") (pintype "bidirectional"))
      (node (ref "R152") (pin "2") (pinfunction "2_2") (pintype "passive"))
    )
    (net (code "155") (name "Net-(R437-Pad2)") (class "Default")
      (node (ref "R437") (pin "2") (pinfunction "2_2") (pintype "passive"))
      (node (ref "R555") (pin "1") (pinfunction "1_1") (pintype "passive"))
      (node (ref "SW1") (pin "4") (pinfunction "4_4") (pintype "bidirectional"))
    )
    (net (code "156") (name "Net-(T16-G)") (class "Default")
      (node (ref "R126") (pin "1") (pinfunction "1_1") (pintype "passive"))
      (node (ref "R127") (pin "2") (pinfunction "2_2") (pintype "passive"))
      (node (ref "T16") (pin "1") (pinfunction "G_1") (pintype "passive"))
    )
    (net (code "157") (name "P3V3MP") (class "Default")
      (node (ref "C21") (pin "2") (pinfunction "2_2") (pintype "passive"))
      (node (ref "C22") (pin "2") (pinfunction "2_2") (pintype "passive"))
      (node (ref "C23") (pin "2") (pinfunction "2_2") (pintype "passive"))
      (node (ref "C24") (pin "2") (pinfunction "2_2") (pintype "passive"))
      (node (ref "C25") (pin "2") (pinfunction "2_2") (pintype "passive"))
      (node (ref "C26") (pin "2") (pinfunction "2_2") (pintype "passive"))
      (node (ref "C27") (pin "2") (pinfunction "2_2") (pintype "passive"))
      (node (ref "C452") (pin "1") (pinfunction "1_1") (pintype "passive"))
      (node (ref "C496") (pin "1") (pinfunction "1_1") (pintype "passive"))
      (node (ref "FB1") (pin "2") (pinfunction "2_2") (pintype "passive"))
      (node (ref "IC1") (pin "19") (pinfunction "VBAT_19") (pintype "power_in"))
      (node (ref "IC1") (pin "28") (pinfunction "VDD(3V3)_28") (pintype "power_in"))
      (node (ref "IC1") (pin "42") (pinfunction "VDD(REG)(3V3)_42") (pintype "power_in"))
      (node (ref "IC1") (pin "54") (pinfunction "VDD(3V3)_54") (pintype "power_in"))
      (node (ref "IC1") (pin "71") (pinfunction "VDD(3V3)_71") (pintype "power_in"))
      (node (ref "IC1") (pin "84") (pinfunction "VDD(REG)(3V3)_84") (pintype "power_in"))
      (node (ref "IC1") (pin "96") (pinfunction "VDD(3V3)_96") (pintype "power_in"))
      (node (ref "IC3") (pin "5") (pinfunction "SENSE_5") (pintype "input"))
      (node (ref "IC3") (pin "6") (pinfunction "VDD_6") (pintype "power_in"))
      (node (ref "IC45") (pin "5") (pinfunction "VCC_5") (pintype "power_in"))
      (node (ref "IC66") (pin "20") (pinfunction "VDD_20") (pintype "power_in"))
      (node (ref "J17") (pin "1") (pinfunction "1_1") (pintype "passive"))
      (node (ref "J17") (pin "2") (pinfunction "2_2") (pintype "passive"))
      (node (ref "J9") (pin "1") (pinfunction "1_1") (pintype "bidirectional"))
      (node (ref "LED1") (pin "1") (pinfunction "A_1") (pintype "passive"))
      (node (ref "LED17") (pin "2") (pinfunction "A_2") (pintype "passive"))
      (node (ref "LED2") (pin "1") (pinfunction "A_1") (pintype "passive"))
      (node (ref "R100") (pin "2") (pinfunction "2_2") (pintype "passive"))
      (node (ref "R101") (pin "2") (pinfunction "2_2") (pintype "passive"))
      (node (ref "R102") (pin "2") (pinfunction "2_2") (pintype "passive"))
      (node (ref "R121") (pin "1") (pinfunction "1_1") (pintype "passive"))
      (node (ref "R125") (pin "2") (pinfunction "2_2") (pintype "passive"))
      (node (ref "R169") (pin "1") (pinfunction "1_1") (pintype "passive"))
      (node (ref "R19") (pin "2") (pinfunction "2_2") (pintype "passive"))
      (node (ref "R2") (pin "2") (pinfunction "2_2") (pintype "passive"))
      (node (ref "R238") (pin "2") (pinfunction "2_2") (pintype "passive"))
      (node (ref "R3") (pin "2") (pinfunction "2_2") (pintype "passive"))
      (node (ref "R31") (pin "2") (pinfunction "2_2") (pintype "passive"))
      (node (ref "R33") (pin "2") (pinfunction "2_2") (pintype "passive"))
      (node (ref "R34") (pin "2") (pinfunction "2_2") (pintype "passive"))
      (node (ref "R4") (pin "2") (pinfunction "2_2") (pintype "passive"))
      (node (ref "R456") (pin "2") (pinfunction "2_2") (pintype "passive"))
      (node (ref "R47") (pin "1") (pinfunction "1_1") (pintype "passive"))
      (node (ref "R6") (pin "2") (pinfunction "2_2") (pintype "passive"))
      (node (ref "R97") (pin "2") (pinfunction "2_2") (pintype "passive"))
      (node (ref "R98") (pin "2") (pinfunction "2_2") (pintype "passive"))
      (node (ref "R99") (pin "2") (pinfunction "2_2") (pintype "passive"))
    )
    (net (code "158") (name "P12V") (class "Default")
      (node (ref "R471") (pin "2") (pinfunction "2_2") (pintype "passive"))
    )
    (net (code "159") (name "P12V_AUX") (class "Default")
      (node (ref "R126") (pin "2") (pinfunction "2_2") (pintype "passive"))
    )
    (net (code "160") (name "unconnected-(IC1A-NC-Pad13)") (class "Default")
      (node (ref "IC1") (pin "13") (pinfunction "NC_13") (pintype "passive"))
    )
    (net (code "161") (name "unconnected-(IC1A-P0[9]{slash}I2STX_SDA{slash}MOSI1{slash}MAT2[3]-Pad76)") (class "Default")
      (node (ref "IC1") (pin "76") (pinfunction "P0[9]/I2STX_SDA/MOSI1/MAT2[3]_76") (pintype "bidirectional"))
    )
    (net (code "162") (name "unconnected-(IC1A-P0[17]{slash}CTS1{slash}MISO0{slash}MISO-Pad61)") (class "Default")
      (node (ref "IC1") (pin "61") (pinfunction "P0[17]/CTS1/MISO0/MISO_61") (pintype "bidirectional"))
    )
    (net (code "163") (name "unconnected-(IC1A-P0[21]{slash}RI1{slash}RD1-Pad57)") (class "Default")
      (node (ref "IC1") (pin "57") (pinfunction "P0[21]/RI1/RD1_57") (pintype "bidirectional"))
    )
    (net (code "164") (name "unconnected-(IC1A-P0[30]{slash}USB_D--Pad30)") (class "Default")
      (node (ref "IC1") (pin "30") (pinfunction "P0[30]/USB_D-_30") (pintype "bidirectional"))
    )
    (net (code "165") (name "unconnected-(IC1A-RTCK-Pad100)") (class "Default")
      (node (ref "IC1") (pin "100") (pinfunction "RTCK_100") (pintype "output"))
    )
    (net (code "166") (name "unconnected-(IC1A-RTCX1-Pad16)") (class "Default")
      (node (ref "IC1") (pin "16") (pinfunction "RTCX1_16") (pintype "input+no_connect"))
    )
    (net (code "167") (name "unconnected-(IC1A-RTCX2-Pad18)") (class "Default")
      (node (ref "IC1") (pin "18") (pinfunction "RTCX2_18") (pintype "output"))
    )
    (net (code "168") (name "unconnected-(IC1A-~{RSTOUT}-Pad14)") (class "Default")
      (node (ref "IC1") (pin "14") (pinfunction "~{RSTOUT}_14") (pintype "output"))
    )
    (net (code "169") (name "unconnected-(IC4-C1-Pad1)") (class "Default")
      (node (ref "IC4") (pin "1") (pinfunction "C1_1") (pintype "passive"))
    )
    (net (code "170") (name "unconnected-(IC4-C2-Pad3)") (class "Default")
      (node (ref "IC4") (pin "3") (pinfunction "C2_3") (pintype "passive"))
    )
    (net (code "171") (name "unconnected-(IC5-C4-Pad6)") (class "Default")
      (node (ref "IC5") (pin "6") (pinfunction "C4_6") (pintype "passive"))
    )
    (net (code "172") (name "unconnected-(IC66-TP-Pad10)") (class "Default")
      (node (ref "IC66") (pin "10") (pinfunction "TP_10") (pintype "passive+no_connect"))
    )
    (net (code "173") (name "unconnected-(IC66-~{INT}-Pad6)") (class "Default")
      (node (ref "IC66") (pin "6") (pinfunction "~{INT}_6") (pintype "output+no_connect"))
    )
    (net (code "174") (name "unconnected-(J9-Pad7)") (class "Default")
      (node (ref "J9") (pin "7") (pinfunction "7_7") (pintype "bidirectional"))
    )
    (net (code "175") (name "unconnected-(SW1-Pad2)") (class "Default")
      (node (ref "SW1") (pin "2") (pinfunction "2_2") (pintype "bidirectional"))
    )
    (net (code "176") (name "unconnected-(SW1-Pad7)") (class "Default")
      (node (ref "SW1") (pin "7") (pinfunction "7_7") (pintype "bidirectional"))
    )
  )
)
